# SCH_OpenIDS2.net
KiCad netlist of a schematic drawn in EasyEDA
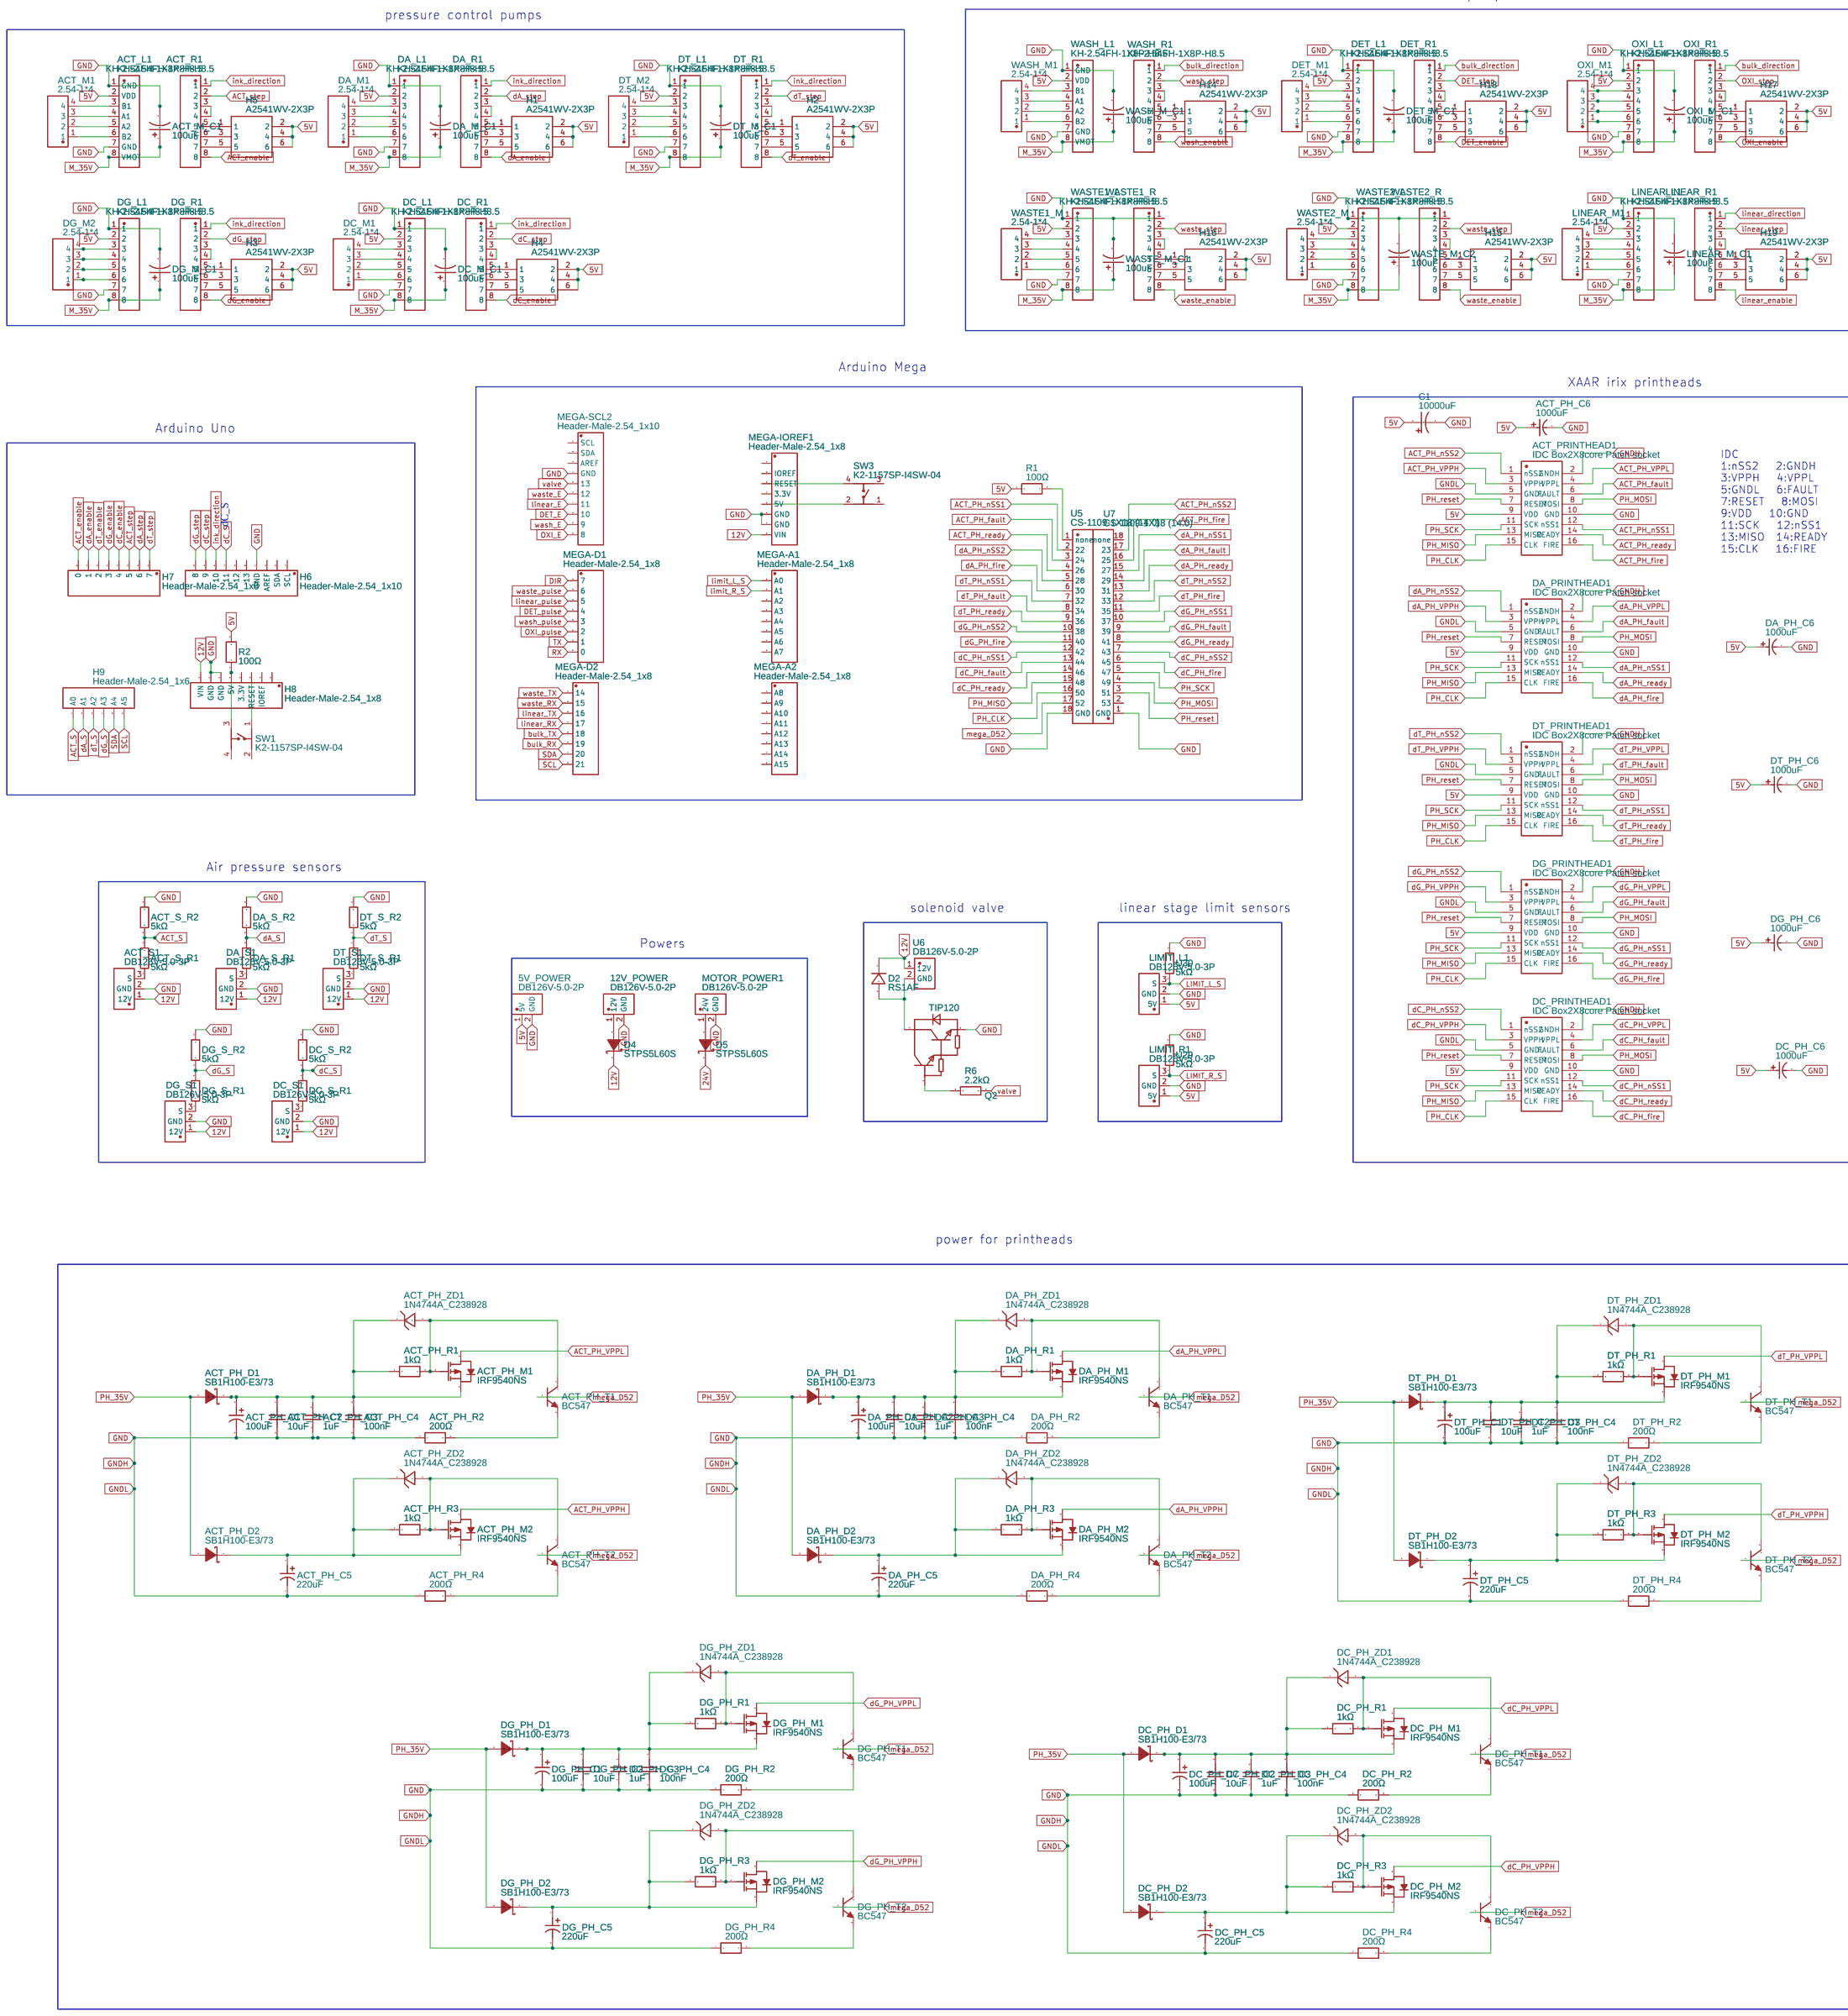
[diagram p0: schematic sheet]

(export (version "E")
  (design (tool "Eeschema 10.0.6"))
  (components
    (comp (ref "5V_POWER")
      (value "DB126V-5.0-2P")
      (fields
        (field (name "Manufacturer Part") "DB126V-5.0-2P-GN-P")
        (field (name "Manufacturer") "DORABO(地博电气)")
      )
      (libsource (lib "") (part "DB126V-5.0-2P"))
    )
    (comp (ref "12V_POWER")
      (value "DB126V-5.0-2P")
      (fields
        (field (name "Manufacturer Part") "DB126V-5.0-2P-GN-P")
        (field (name "Manufacturer") "DORABO(地博电气)")
      )
      (libsource (lib "") (part "DB126V-5.0-2P_2"))
    )
    (comp (ref "ACT_L1")
      (value "KH-2.54FH-1X8P-H8.5")
      (fields (field (name "Manufacturer") "kinghelm(金航标)"))
      (libsource (lib "") (part "KH-2.54FH-1X8P-H8.5_4"))
    )
    (comp (ref "ACT_M1")
      (value "2.54-1*4")
      (fields (field (name "Manufacturer") "ZHOURI(洲日)"))
      (libsource (lib "") (part "2.54-1*4_7"))
    )
    (comp (ref "ACT_M_C1")
      (value "100uF")
      (fields
        (field (name "Manufacturer Part") "50YXF100MEFCCE8X11.5")
        (field (name "Manufacturer") "rubycon(红宝石)")
      )
      (libsource (lib "") (part "50YXF100MEFCCE8X11.5"))
    )
    (comp (ref "ACT_PH_C1")
      (value "100uF")
      (fields (field (name "Manufacturer Part") "1011001013R00") (field (name "Manufacturer") "NJCON(永立)"))
      (libsource (lib "") (part "1011001013R00_4"))
    )
    (comp (ref "ACT_PH_C2")
      (value "10uF")
      (fields (field (name "Manufacturer Part") "C1210X106K050T") (field (name "Manufacturer") "IHHEC(禾伸堂)"))
      (libsource (lib "") (part "C1210X106K050T_3"))
    )
    (comp (ref "ACT_PH_C3")
      (value "1uF")
      (fields (field (name "Manufacturer Part") "1210B105K101NT") (field (name "Manufacturer") "FH(风华)"))
      (libsource (lib "") (part "1210B105K101NT_4"))
    )
    (comp (ref "ACT_PH_C4")
      (value "100nF")
      (fields (field (name "Manufacturer Part") "C1005X7R1H104KT000S") (field (name "Manufacturer") "TDK"))
      (libsource (lib "") (part "C1005X7R1H104KT000S"))
    )
    (comp (ref "ACT_PH_C5")
      (value "220uF")
      (fields
        (field (name "Manufacturer Part") "RVT1H221M1010 220UF 50V")
        (field (name "Manufacturer") "DMBJ(振宝佳)")
      )
      (libsource (lib "") (part "RVT1H221M1010 220UF 50V"))
    )
    (comp (ref "ACT_PH_C6")
      (value "1000uF")
      (fields (field (name "Manufacturer Part") "KF102M010F140A") (field (name "Manufacturer") "CapXon(丰宾)"))
      (libsource (lib "") (part "KF102M010F140A_4"))
    )
    (comp (ref "ACT_PH_D1")
      (value "SB1H100-E3/73")
      (fields (field (name "Manufacturer") "VISHAY(威世)"))
      (libsource (lib "") (part "SB1H100-E3/73_4"))
    )
    (comp (ref "ACT_PH_D2")
      (value "SB1H100-E3/73")
      (fields (field (name "Manufacturer") "VISHAY(威世)"))
      (libsource (lib "") (part "SB1H100-E3/73_4"))
    )
    (comp (ref "ACT_PH_M1")
      (value "IRF9540NS")
      (fields (field (name "Manufacturer") "minos(迈诺斯)"))
      (libsource (lib "") (part "IRF9540NS_4"))
    )
    (comp (ref "ACT_PH_M2")
      (value "IRF9540NS")
      (fields (field (name "Manufacturer") "minos(迈诺斯)"))
      (libsource (lib "") (part "IRF9540NS_4"))
    )
    (comp (ref "ACT_PH_R1")
      (value "1kΩ")
      (fields
        (field (name "Manufacturer Part") "HoCR2512-2W-1KR-5%")
        (field (name "Manufacturer") "Milliohm(毫欧)")
      )
      (libsource (lib "") (part "HOCR2512-2W-1KR-5%_2"))
    )
    (comp (ref "ACT_PH_R2")
      (value "200Ω")
      (fields (field (name "Manufacturer Part") "CR1/4W-200Ω±5%-ST52") (field (name "Manufacturer") "VO(翔胜)"))
      (libsource (lib "") (part "CR1/4W-200Ω±5%-ST52_4"))
    )
    (comp (ref "ACT_PH_R3")
      (value "1kΩ")
      (fields
        (field (name "Manufacturer Part") "HoCR2512-2W-1KR-5%")
        (field (name "Manufacturer") "Milliohm(毫欧)")
      )
      (libsource (lib "") (part "HOCR2512-2W-1KR-5%_2"))
    )
    (comp (ref "ACT_PH_R4")
      (value "200Ω")
      (fields (field (name "Manufacturer Part") "CR1/4W-200Ω±5%-ST52") (field (name "Manufacturer") "VO(翔胜)"))
      (libsource (lib "") (part "CR1/4W-200Ω±5%-ST52_4"))
    )
    (comp (ref "ACT_PH_T1")
      (value "BC547")
      (fields
        (field (name "Manufacturer Part") "BC547(RANGE:420-800)")
        (field (name "Manufacturer") "CJ(江苏长电/长晶)")
      )
      (libsource (lib "") (part "BC547_3"))
    )
    (comp (ref "ACT_PH_T2")
      (value "BC547")
      (fields
        (field (name "Manufacturer Part") "BC547(RANGE:420-800)")
        (field (name "Manufacturer") "CJ(江苏长电/长晶)")
      )
      (libsource (lib "") (part "BC547_3"))
    )
    (comp (ref "ACT_PH_ZD1")
      (value "1N4744A_C238928")
      (fields (field (name "Manufacturer Part") "1N4744A") (field (name "Manufacturer") "onsemi(安森美)"))
      (libsource (lib "") (part "1N4744A_C238928_1"))
    )
    (comp (ref "ACT_PH_ZD2")
      (value "1N4744A_C238928")
      (fields (field (name "Manufacturer Part") "1N4744A") (field (name "Manufacturer") "onsemi(安森美)"))
      (libsource (lib "") (part "1N4744A_C238928_1"))
    )
    (comp (ref "ACT_PRINTHEAD1")
      (value "IDC Box2X8core Patch socket")
      (fields (field (name "Manufacturer Part") "2.0-2*8P立贴简牛") (field (name "Manufacturer") "BOOMELE(博穆精密)"))
      (libsource (lib "") (part "IDC Box2X8core Patch socket"))
    )
    (comp (ref "ACT_R1")
      (value "KH-2.54FH-1X8P-H8.5")
      (fields (field (name "Manufacturer") "kinghelm(金航标)"))
      (libsource (lib "") (part "KH-2.54FH-1X8P-H8.5_7"))
    )
    (comp (ref "ACT_S1")
      (value "DB126V-5.0-3P")
      (fields
        (field (name "Manufacturer Part") "DB126V-5.0-3P-GN")
        (field (name "Manufacturer") "DORABO(地博电气)")
      )
      (libsource (lib "") (part "DB126V-5.0-3P_6"))
    )
    (comp (ref "ACT_S_R1")
      (value "5kΩ")
      (fields (field (name "Manufacturer Part") "RT0603BRE075KL") (field (name "Manufacturer") "YAGEO(国巨)"))
      (libsource (lib "") (part "RT0603BRE075KL_1"))
    )
    (comp (ref "ACT_S_R2")
      (value "5kΩ")
      (fields (field (name "Manufacturer Part") "RT0603BRE075KL") (field (name "Manufacturer") "YAGEO(国巨)"))
      (libsource (lib "") (part "RT0603BRE075KL_1"))
    )
    (comp (ref "C1")
      (value "10000uF")
      (fields
        (field (name "Manufacturer Part") "KM1C103ML350A00CV0")
        (field (name "Manufacturer") "HUAWEI(华威集团)")
      )
      (libsource (lib "") (part "KM1C103ML350A00CV0"))
    )
    (comp (ref "D2")
      (value "RS1AF")
      (fields (field (name "Manufacturer") "SHIKUES(时科)"))
      (libsource (lib "") (part "RS1AF"))
    )
    (comp (ref "D4")
      (value "STPS5L60S")
      (fields (field (name "Manufacturer") "ST(意法半导体)"))
      (libsource (lib "") (part "STPS5L60S"))
    )
    (comp (ref "D5")
      (value "STPS5L60S")
      (fields (field (name "Manufacturer") "ST(意法半导体)"))
      (libsource (lib "") (part "STPS5L60S"))
    )
    (comp (ref "DA_L1")
      (value "KH-2.54FH-1X8P-H8.5")
      (fields (field (name "Manufacturer") "kinghelm(金航标)"))
      (libsource (lib "") (part "KH-2.54FH-1X8P-H8.5_20"))
    )
    (comp (ref "DA_M1")
      (value "2.54-1*4")
      (fields (field (name "Manufacturer") "ZHOURI(洲日)"))
      (libsource (lib "") (part "2.54-1*4_6"))
    )
    (comp (ref "DA_M_C1")
      (value "100uF")
      (fields
        (field (name "Manufacturer Part") "50YXF100MEFCCE8X11.5")
        (field (name "Manufacturer") "rubycon(红宝石)")
      )
      (libsource (lib "") (part "50YXF100MEFCCE8X11.5_7"))
    )
    (comp (ref "DA_PH_C1")
      (value "100uF")
      (fields (field (name "Manufacturer Part") "1011001013R00") (field (name "Manufacturer") "NJCON(永立)"))
      (libsource (lib "") (part "1011001013R00_3"))
    )
    (comp (ref "DA_PH_C2")
      (value "10uF")
      (fields (field (name "Manufacturer Part") "C1210X106K050T") (field (name "Manufacturer") "IHHEC(禾伸堂)"))
      (libsource (lib "") (part "C1210X106K050T"))
    )
    (comp (ref "DA_PH_C3")
      (value "1uF")
      (fields (field (name "Manufacturer Part") "1210B105K101NT") (field (name "Manufacturer") "FH(风华)"))
      (libsource (lib "") (part "1210B105K101NT"))
    )
    (comp (ref "DA_PH_C4")
      (value "100nF")
      (fields (field (name "Manufacturer Part") "C1005X7R1H104KT000S") (field (name "Manufacturer") "TDK"))
      (libsource (lib "") (part "C1005X7R1H104KT000S_3"))
    )
    (comp (ref "DA_PH_C5")
      (value "220uF")
      (fields
        (field (name "Manufacturer Part") "RVT1H221M1010 220UF 50V")
        (field (name "Manufacturer") "DMBJ(振宝佳)")
      )
      (libsource (lib "") (part "RVT1H221M1010 220UF 50V_3"))
    )
    (comp (ref "DA_PH_C6")
      (value "1000uF")
      (fields (field (name "Manufacturer Part") "KF102M010F140A") (field (name "Manufacturer") "CapXon(丰宾)"))
      (libsource (lib "") (part "KF102M010F140A_2"))
    )
    (comp (ref "DA_PH_D1")
      (value "SB1H100-E3/73")
      (fields (field (name "Manufacturer") "VISHAY(威世)"))
      (libsource (lib "") (part "SB1H100-E3/73_1"))
    )
    (comp (ref "DA_PH_D2")
      (value "SB1H100-E3/73")
      (fields (field (name "Manufacturer") "VISHAY(威世)"))
      (libsource (lib "") (part "SB1H100-E3/73_1"))
    )
    (comp (ref "DA_PH_M1")
      (value "IRF9540NS")
      (fields (field (name "Manufacturer") "minos(迈诺斯)"))
      (libsource (lib "") (part "IRF9540NS_1"))
    )
    (comp (ref "DA_PH_M2")
      (value "IRF9540NS")
      (fields (field (name "Manufacturer") "minos(迈诺斯)"))
      (libsource (lib "") (part "IRF9540NS_1"))
    )
    (comp (ref "DA_PH_R1")
      (value "1kΩ")
      (fields
        (field (name "Manufacturer Part") "HoCR2512-2W-1KR-5%")
        (field (name "Manufacturer") "Milliohm(毫欧)")
      )
      (libsource (lib "") (part "HOCR2512-2W-1KR-5%"))
    )
    (comp (ref "DA_PH_R2")
      (value "200Ω")
      (fields (field (name "Manufacturer Part") "CR1/4W-200Ω±5%-ST52") (field (name "Manufacturer") "VO(翔胜)"))
      (libsource (lib "") (part "CR1/4W-200Ω±5%-ST52"))
    )
    (comp (ref "DA_PH_R3")
      (value "1kΩ")
      (fields
        (field (name "Manufacturer Part") "HoCR2512-2W-1KR-5%")
        (field (name "Manufacturer") "Milliohm(毫欧)")
      )
      (libsource (lib "") (part "HOCR2512-2W-1KR-5%"))
    )
    (comp (ref "DA_PH_R4")
      (value "200Ω")
      (fields (field (name "Manufacturer Part") "CR1/4W-200Ω±5%-ST52") (field (name "Manufacturer") "VO(翔胜)"))
      (libsource (lib "") (part "CR1/4W-200Ω±5%-ST52"))
    )
    (comp (ref "DA_PH_T1")
      (value "BC547")
      (fields
        (field (name "Manufacturer Part") "BC547(RANGE:420-800)")
        (field (name "Manufacturer") "CJ(江苏长电/长晶)")
      )
      (libsource (lib "") (part "BC547"))
    )
    (comp (ref "DA_PH_T2")
      (value "BC547")
      (fields
        (field (name "Manufacturer Part") "BC547(RANGE:420-800)")
        (field (name "Manufacturer") "CJ(江苏长电/长晶)")
      )
      (libsource (lib "") (part "BC547"))
    )
    (comp (ref "DA_PH_ZD1")
      (value "1N4744A_C238928")
      (fields (field (name "Manufacturer Part") "1N4744A") (field (name "Manufacturer") "onsemi(安森美)"))
      (libsource (lib "") (part "1N4744A_C238928"))
    )
    (comp (ref "DA_PH_ZD2")
      (value "1N4744A_C238928")
      (fields (field (name "Manufacturer Part") "1N4744A") (field (name "Manufacturer") "onsemi(安森美)"))
      (libsource (lib "") (part "1N4744A_C238928"))
    )
    (comp (ref "DA_PRINTHEAD1")
      (value "IDC Box2X8core Patch socket")
      (fields (field (name "Manufacturer Part") "2.0-2*8P立贴简牛") (field (name "Manufacturer") "BOOMELE(博穆精密)"))
      (libsource (lib "") (part "IDC Box2X8core Patch socket_1"))
    )
    (comp (ref "DA_R1")
      (value "KH-2.54FH-1X8P-H8.5")
      (fields (field (name "Manufacturer") "kinghelm(金航标)"))
      (libsource (lib "") (part "KH-2.54FH-1X8P-H8.5_15"))
    )
    (comp (ref "DA_S1")
      (value "DB126V-5.0-3P")
      (fields
        (field (name "Manufacturer Part") "DB126V-5.0-3P-GN")
        (field (name "Manufacturer") "DORABO(地博电气)")
      )
      (libsource (lib "") (part "DB126V-5.0-3P_3"))
    )
    (comp (ref "DA_S_R1")
      (value "5kΩ")
      (fields (field (name "Manufacturer Part") "RT0603BRE075KL") (field (name "Manufacturer") "YAGEO(国巨)"))
      (libsource (lib "") (part "RT0603BRE075KL"))
    )
    (comp (ref "DA_S_R2")
      (value "5kΩ")
      (fields (field (name "Manufacturer Part") "RT0603BRE075KL") (field (name "Manufacturer") "YAGEO(国巨)"))
      (libsource (lib "") (part "RT0603BRE075KL"))
    )
    (comp (ref "DC_L1")
      (value "KH-2.54FH-1X8P-H8.5")
      (fields (field (name "Manufacturer") "kinghelm(金航标)"))
      (libsource (lib "") (part "KH-2.54FH-1X8P-H8.5_5"))
    )
    (comp (ref "DC_M1")
      (value "2.54-1*4")
      (fields (field (name "Manufacturer") "ZHOURI(洲日)"))
      (libsource (lib "") (part "2.54-1*4_1"))
    )
    (comp (ref "DC_M_C1")
      (value "100uF")
      (fields
        (field (name "Manufacturer Part") "50YXF100MEFCCE8X11.5")
        (field (name "Manufacturer") "rubycon(红宝石)")
      )
      (libsource (lib "") (part "50YXF100MEFCCE8X11.5_5"))
    )
    (comp (ref "DC_PH_C2")
      (value "10uF")
      (fields (field (name "Manufacturer Part") "C1210X106K050T") (field (name "Manufacturer") "IHHEC(禾伸堂)"))
      (libsource (lib "") (part "C1210X106K050T_2"))
    )
    (comp (ref "DC_PH_C3")
      (value "1uF")
      (fields (field (name "Manufacturer Part") "1210B105K101NT") (field (name "Manufacturer") "FH(风华)"))
      (libsource (lib "") (part "1210B105K101NT_3"))
    )
    (comp (ref "DC_PH_C4")
      (value "100nF")
      (fields (field (name "Manufacturer Part") "C1005X7R1H104KT000S") (field (name "Manufacturer") "TDK"))
      (libsource (lib "") (part "C1005X7R1H104KT000S_1"))
    )
    (comp (ref "DC_PH_C5")
      (value "220uF")
      (fields
        (field (name "Manufacturer Part") "RVT1H221M1010 220UF 50V")
        (field (name "Manufacturer") "DMBJ(振宝佳)")
      )
      (libsource (lib "") (part "RVT1H221M1010 220UF 50V_1"))
    )
    (comp (ref "DC_PH_C6")
      (value "1000uF")
      (fields (field (name "Manufacturer Part") "KF102M010F140A") (field (name "Manufacturer") "CapXon(丰宾)"))
      (libsource (lib "") (part "KF102M010F140A_3"))
    )
    (comp (ref "DC_PH_C7")
      (value "100uF")
      (fields (field (name "Manufacturer Part") "1011001013R00") (field (name "Manufacturer") "NJCON(永立)"))
      (libsource (lib "") (part "1011001013R00_2"))
    )
    (comp (ref "DC_PH_D1")
      (value "SB1H100-E3/73")
      (fields (field (name "Manufacturer") "VISHAY(威世)"))
      (libsource (lib "") (part "SB1H100-E3/73"))
    )
    (comp (ref "DC_PH_D2")
      (value "SB1H100-E3/73")
      (fields (field (name "Manufacturer") "VISHAY(威世)"))
      (libsource (lib "") (part "SB1H100-E3/73"))
    )
    (comp (ref "DC_PH_M1")
      (value "IRF9540NS")
      (fields (field (name "Manufacturer") "minos(迈诺斯)"))
      (libsource (lib "") (part "IRF9540NS_2"))
    )
    (comp (ref "DC_PH_M2")
      (value "IRF9540NS")
      (fields (field (name "Manufacturer") "minos(迈诺斯)"))
      (libsource (lib "") (part "IRF9540NS_2"))
    )
    (comp (ref "DC_PH_R1")
      (value "1kΩ")
      (fields
        (field (name "Manufacturer Part") "HoCR2512-2W-1KR-5%")
        (field (name "Manufacturer") "Milliohm(毫欧)")
      )
      (libsource (lib "") (part "HOCR2512-2W-1KR-5%_3"))
    )
    (comp (ref "DC_PH_R2")
      (value "200Ω")
      (fields (field (name "Manufacturer Part") "CR1/4W-200Ω±5%-ST52") (field (name "Manufacturer") "VO(翔胜)"))
      (libsource (lib "") (part "CR1/4W-200Ω±5%-ST52_3"))
    )
    (comp (ref "DC_PH_R3")
      (value "1kΩ")
      (fields
        (field (name "Manufacturer Part") "HoCR2512-2W-1KR-5%")
        (field (name "Manufacturer") "Milliohm(毫欧)")
      )
      (libsource (lib "") (part "HOCR2512-2W-1KR-5%_3"))
    )
    (comp (ref "DC_PH_R4")
      (value "200Ω")
      (fields (field (name "Manufacturer Part") "CR1/4W-200Ω±5%-ST52") (field (name "Manufacturer") "VO(翔胜)"))
      (libsource (lib "") (part "CR1/4W-200Ω±5%-ST52_3"))
    )
    (comp (ref "DC_PH_T1")
      (value "BC547")
      (fields
        (field (name "Manufacturer Part") "BC547(RANGE:420-800)")
        (field (name "Manufacturer") "CJ(江苏长电/长晶)")
      )
      (libsource (lib "") (part "BC547_2"))
    )
    (comp (ref "DC_PH_T2")
      (value "BC547")
      (fields
        (field (name "Manufacturer Part") "BC547(RANGE:420-800)")
        (field (name "Manufacturer") "CJ(江苏长电/长晶)")
      )
      (libsource (lib "") (part "BC547_2"))
    )
    (comp (ref "DC_PH_ZD1")
      (value "1N4744A_C238928")
      (fields (field (name "Manufacturer Part") "1N4744A") (field (name "Manufacturer") "onsemi(安森美)"))
      (libsource (lib "") (part "1N4744A_C238928_2"))
    )
    (comp (ref "DC_PH_ZD2")
      (value "1N4744A_C238928")
      (fields (field (name "Manufacturer Part") "1N4744A") (field (name "Manufacturer") "onsemi(安森美)"))
      (libsource (lib "") (part "1N4744A_C238928_2"))
    )
    (comp (ref "DC_PRINTHEAD1")
      (value "IDC Box2X8core Patch socket")
      (fields (field (name "Manufacturer Part") "2.0-2*8P立贴简牛") (field (name "Manufacturer") "BOOMELE(博穆精密)"))
      (libsource (lib "") (part "IDC Box2X8core Patch socket_2"))
    )
    (comp (ref "DC_R1")
      (value "KH-2.54FH-1X8P-H8.5")
      (fields (field (name "Manufacturer") "kinghelm(金航标)"))
      (libsource (lib "") (part "KH-2.54FH-1X8P-H8.5_18"))
    )
    (comp (ref "DC_S1")
      (value "DB126V-5.0-3P")
      (fields
        (field (name "Manufacturer Part") "DB126V-5.0-3P-GN")
        (field (name "Manufacturer") "DORABO(地博电气)")
      )
      (libsource (lib "") (part "DB126V-5.0-3P_4"))
    )
    (comp (ref "DC_S_R1")
      (value "5kΩ")
      (fields (field (name "Manufacturer Part") "RT0603BRE075KL") (field (name "Manufacturer") "YAGEO(国巨)"))
      (libsource (lib "") (part "RT0603BRE075KL_2"))
    )
    (comp (ref "DC_S_R2")
      (value "5kΩ")
      (fields (field (name "Manufacturer Part") "RT0603BRE075KL") (field (name "Manufacturer") "YAGEO(国巨)"))
      (libsource (lib "") (part "RT0603BRE075KL_2"))
    )
    (comp (ref "DET_L1")
      (value "KH-2.54FH-1X8P-H8.5")
      (fields (field (name "Manufacturer") "kinghelm(金航标)"))
      (libsource (lib "") (part "KH-2.54FH-1X8P-H8.5_12"))
    )
    (comp (ref "DET_M1")
      (value "2.54-1*4")
      (fields (field (name "Manufacturer") "ZHOURI(洲日)"))
      (libsource (lib "") (part "2.54-1*4_4"))
    )
    (comp (ref "DET_M_C1")
      (value "100uF")
      (fields
        (field (name "Manufacturer Part") "50YXF100MEFCCE8X11.5")
        (field (name "Manufacturer") "rubycon(红宝石)")
      )
      (libsource (lib "") (part "50YXF100MEFCCE8X11.5_8"))
    )
    (comp (ref "DET_R1")
      (value "KH-2.54FH-1X8P-H8.5")
      (fields (field (name "Manufacturer") "kinghelm(金航标)"))
      (libsource (lib "") (part "KH-2.54FH-1X8P-H8.5_3"))
    )
    (comp (ref "DG_L1")
      (value "KH-2.54FH-1X8P-H8.5")
      (fields (field (name "Manufacturer") "kinghelm(金航标)"))
      (libsource (lib "") (part "KH-2.54FH-1X8P-H8.5_1"))
    )
    (comp (ref "DG_M2")
      (value "2.54-1*4")
      (fields (field (name "Manufacturer") "ZHOURI(洲日)"))
      (libsource (lib "") (part "2.54-1*4_5"))
    )
    (comp (ref "DG_M_C1")
      (value "100uF")
      (fields
        (field (name "Manufacturer Part") "50YXF100MEFCCE8X11.5")
        (field (name "Manufacturer") "rubycon(红宝石)")
      )
      (libsource (lib "") (part "50YXF100MEFCCE8X11.5_1"))
    )
    (comp (ref "DG_PH_C1")
      (value "100uF")
      (fields (field (name "Manufacturer Part") "1011001013R00") (field (name "Manufacturer") "NJCON(永立)"))
      (libsource (lib "") (part "1011001013R00"))
    )
    (comp (ref "DG_PH_C2")
      (value "10uF")
      (fields (field (name "Manufacturer Part") "C1210X106K050T") (field (name "Manufacturer") "IHHEC(禾伸堂)"))
      (libsource (lib "") (part "C1210X106K050T_1"))
    )
    (comp (ref "DG_PH_C3")
      (value "1uF")
      (fields (field (name "Manufacturer Part") "1210B105K101NT") (field (name "Manufacturer") "FH(风华)"))
      (libsource (lib "") (part "1210B105K101NT_2"))
    )
    (comp (ref "DG_PH_C4")
      (value "100nF")
      (fields (field (name "Manufacturer Part") "C1005X7R1H104KT000S") (field (name "Manufacturer") "TDK"))
      (libsource (lib "") (part "C1005X7R1H104KT000S_4"))
    )
    (comp (ref "DG_PH_C5")
      (value "220uF")
      (fields
        (field (name "Manufacturer Part") "RVT1H221M1010 220UF 50V")
        (field (name "Manufacturer") "DMBJ(振宝佳)")
      )
      (libsource (lib "") (part "RVT1H221M1010 220UF 50V_4"))
    )
    (comp (ref "DG_PH_C6")
      (value "1000uF")
      (fields (field (name "Manufacturer Part") "KF102M010F140A") (field (name "Manufacturer") "CapXon(丰宾)"))
      (libsource (lib "") (part "KF102M010F140A"))
    )
    (comp (ref "DG_PH_D1")
      (value "SB1H100-E3/73")
      (fields (field (name "Manufacturer") "VISHAY(威世)"))
      (libsource (lib "") (part "SB1H100-E3/73_2"))
    )
    (comp (ref "DG_PH_D2")
      (value "SB1H100-E3/73")
      (fields (field (name "Manufacturer") "VISHAY(威世)"))
      (libsource (lib "") (part "SB1H100-E3/73_2"))
    )
    (comp (ref "DG_PH_M1")
      (value "IRF9540NS")
      (fields (field (name "Manufacturer") "minos(迈诺斯)"))
      (libsource (lib "") (part "IRF9540NS_3"))
    )
    (comp (ref "DG_PH_M2")
      (value "IRF9540NS")
      (fields (field (name "Manufacturer") "minos(迈诺斯)"))
      (libsource (lib "") (part "IRF9540NS_3"))
    )
    (comp (ref "DG_PH_R1")
      (value "1kΩ")
      (fields
        (field (name "Manufacturer Part") "HoCR2512-2W-1KR-5%")
        (field (name "Manufacturer") "Milliohm(毫欧)")
      )
      (libsource (lib "") (part "HOCR2512-2W-1KR-5%_4"))
    )
    (comp (ref "DG_PH_R2")
      (value "200Ω")
      (fields (field (name "Manufacturer Part") "CR1/4W-200Ω±5%-ST52") (field (name "Manufacturer") "VO(翔胜)"))
      (libsource (lib "") (part "CR1/4W-200Ω±5%-ST52_1"))
    )
    (comp (ref "DG_PH_R3")
      (value "1kΩ")
      (fields
        (field (name "Manufacturer Part") "HoCR2512-2W-1KR-5%")
        (field (name "Manufacturer") "Milliohm(毫欧)")
      )
      (libsource (lib "") (part "HOCR2512-2W-1KR-5%_4"))
    )
    (comp (ref "DG_PH_R4")
      (value "200Ω")
      (fields (field (name "Manufacturer Part") "CR1/4W-200Ω±5%-ST52") (field (name "Manufacturer") "VO(翔胜)"))
      (libsource (lib "") (part "CR1/4W-200Ω±5%-ST52_1"))
    )
    (comp (ref "DG_PH_T1")
      (value "BC547")
      (fields
        (field (name "Manufacturer Part") "BC547(RANGE:420-800)")
        (field (name "Manufacturer") "CJ(江苏长电/长晶)")
      )
      (libsource (lib "") (part "BC547_1"))
    )
    (comp (ref "DG_PH_T2")
      (value "BC547")
      (fields
        (field (name "Manufacturer Part") "BC547(RANGE:420-800)")
        (field (name "Manufacturer") "CJ(江苏长电/长晶)")
      )
      (libsource (lib "") (part "BC547_1"))
    )
    (comp (ref "DG_PH_ZD1")
      (value "1N4744A_C238928")
      (fields (field (name "Manufacturer Part") "1N4744A") (field (name "Manufacturer") "onsemi(安森美)"))
      (libsource (lib "") (part "1N4744A_C238928_4"))
    )
    (comp (ref "DG_PH_ZD2")
      (value "1N4744A_C238928")
      (fields (field (name "Manufacturer Part") "1N4744A") (field (name "Manufacturer") "onsemi(安森美)"))
      (libsource (lib "") (part "1N4744A_C238928_4"))
    )
    (comp (ref "DG_PRINTHEAD1")
      (value "IDC Box2X8core Patch socket")
      (fields (field (name "Manufacturer Part") "2.0-2*8P立贴简牛") (field (name "Manufacturer") "BOOMELE(博穆精密)"))
      (libsource (lib "") (part "IDC Box2X8core Patch socket_3"))
    )
    (comp (ref "DG_R1")
      (value "KH-2.54FH-1X8P-H8.5")
      (fields (field (name "Manufacturer") "kinghelm(金航标)"))
      (libsource (lib "") (part "KH-2.54FH-1X8P-H8.5_21"))
    )
    (comp (ref "DG_S1")
      (value "DB126V-5.0-3P")
      (fields
        (field (name "Manufacturer Part") "DB126V-5.0-3P-GN")
        (field (name "Manufacturer") "DORABO(地博电气)")
      )
      (libsource (lib "") (part "DB126V-5.0-3P_1"))
    )
    (comp (ref "DG_S_R1")
      (value "5kΩ")
      (fields (field (name "Manufacturer Part") "RT0603BRE075KL") (field (name "Manufacturer") "YAGEO(国巨)"))
      (libsource (lib "") (part "RT0603BRE075KL_4"))
    )
    (comp (ref "DG_S_R2")
      (value "5kΩ")
      (fields (field (name "Manufacturer Part") "RT0603BRE075KL") (field (name "Manufacturer") "YAGEO(国巨)"))
      (libsource (lib "") (part "RT0603BRE075KL_4"))
    )
    (comp (ref "DT_L1")
      (value "KH-2.54FH-1X8P-H8.5")
      (fields (field (name "Manufacturer") "kinghelm(金航标)"))
      (libsource (lib "") (part "KH-2.54FH-1X8P-H8.5_13"))
    )
    (comp (ref "DT_M2")
      (value "2.54-1*4")
      (fields (field (name "Manufacturer") "ZHOURI(洲日)"))
      (libsource (lib "") (part "2.54-1*4_2"))
    )
    (comp (ref "DT_M_C1")
      (value "100uF")
      (fields
        (field (name "Manufacturer Part") "50YXF100MEFCCE8X11.5")
        (field (name "Manufacturer") "rubycon(红宝石)")
      )
      (libsource (lib "") (part "50YXF100MEFCCE8X11.5_2"))
    )
    (comp (ref "DT_PH_C1")
      (value "100uF")
      (fields (field (name "Manufacturer Part") "1011001013R00") (field (name "Manufacturer") "NJCON(永立)"))
      (libsource (lib "") (part "1011001013R00_1"))
    )
    (comp (ref "DT_PH_C2")
      (value "10uF")
      (fields (field (name "Manufacturer Part") "C1210X106K050T") (field (name "Manufacturer") "IHHEC(禾伸堂)"))
      (libsource (lib "") (part "C1210X106K050T_4"))
    )
    (comp (ref "DT_PH_C3")
      (value "1uF")
      (fields (field (name "Manufacturer Part") "1210B105K101NT") (field (name "Manufacturer") "FH(风华)"))
      (libsource (lib "") (part "1210B105K101NT_1"))
    )
    (comp (ref "DT_PH_C4")
      (value "100nF")
      (fields (field (name "Manufacturer Part") "C1005X7R1H104KT000S") (field (name "Manufacturer") "TDK"))
      (libsource (lib "") (part "C1005X7R1H104KT000S_2"))
    )
    (comp (ref "DT_PH_C5")
      (value "220uF")
      (fields
        (field (name "Manufacturer Part") "RVT1H221M1010 220UF 50V")
        (field (name "Manufacturer") "DMBJ(振宝佳)")
      )
      (libsource (lib "") (part "RVT1H221M1010 220UF 50V_2"))
    )
    (comp (ref "DT_PH_C6")
      (value "1000uF")
      (fields (field (name "Manufacturer Part") "KF102M010F140A") (field (name "Manufacturer") "CapXon(丰宾)"))
      (libsource (lib "") (part "KF102M010F140A_1"))
    )
    (comp (ref "DT_PH_D1")
      (value "SB1H100-E3/73")
      (fields (field (name "Manufacturer") "VISHAY(威世)"))
      (libsource (lib "") (part "SB1H100-E3/73_3"))
    )
    (comp (ref "DT_PH_D2")
      (value "SB1H100-E3/73")
      (fields (field (name "Manufacturer") "VISHAY(威世)"))
      (libsource (lib "") (part "SB1H100-E3/73_3"))
    )
    (comp (ref "DT_PH_M1")
      (value "IRF9540NS")
      (fields (field (name "Manufacturer") "minos(迈诺斯)"))
      (libsource (lib "") (part "IRF9540NS"))
    )
    (comp (ref "DT_PH_M2")
      (value "IRF9540NS")
      (fields (field (name "Manufacturer") "minos(迈诺斯)"))
      (libsource (lib "") (part "IRF9540NS"))
    )
    (comp (ref "DT_PH_R1")
      (value "1kΩ")
      (fields
        (field (name "Manufacturer Part") "HoCR2512-2W-1KR-5%")
        (field (name "Manufacturer") "Milliohm(毫欧)")
      )
      (libsource (lib "") (part "HOCR2512-2W-1KR-5%_1"))
    )
    (comp (ref "DT_PH_R2")
      (value "200Ω")
      (fields (field (name "Manufacturer Part") "CR1/4W-200Ω±5%-ST52") (field (name "Manufacturer") "VO(翔胜)"))
      (libsource (lib "") (part "CR1/4W-200Ω±5%-ST52_2"))
    )
    (comp (ref "DT_PH_R3")
      (value "1kΩ")
      (fields
        (field (name "Manufacturer Part") "HoCR2512-2W-1KR-5%")
        (field (name "Manufacturer") "Milliohm(毫欧)")
      )
      (libsource (lib "") (part "HOCR2512-2W-1KR-5%_1"))
    )
    (comp (ref "DT_PH_R4")
      (value "200Ω")
      (fields (field (name "Manufacturer Part") "CR1/4W-200Ω±5%-ST52") (field (name "Manufacturer") "VO(翔胜)"))
      (libsource (lib "") (part "CR1/4W-200Ω±5%-ST52_2"))
    )
    (comp (ref "DT_PH_T1")
      (value "BC547")
      (fields
        (field (name "Manufacturer Part") "BC547(RANGE:420-800)")
        (field (name "Manufacturer") "CJ(江苏长电/长晶)")
      )
      (libsource (lib "") (part "BC547_4"))
    )
    (comp (ref "DT_PH_T2")
      (value "BC547")
      (fields
        (field (name "Manufacturer Part") "BC547(RANGE:420-800)")
        (field (name "Manufacturer") "CJ(江苏长电/长晶)")
      )
      (libsource (lib "") (part "BC547_4"))
    )
    (comp (ref "DT_PH_ZD1")
      (value "1N4744A_C238928")
      (fields (field (name "Manufacturer Part") "1N4744A") (field (name "Manufacturer") "onsemi(安森美)"))
      (libsource (lib "") (part "1N4744A_C238928_3"))
    )
    (comp (ref "DT_PH_ZD2")
      (value "1N4744A_C238928")
      (fields (field (name "Manufacturer Part") "1N4744A") (field (name "Manufacturer") "onsemi(安森美)"))
      (libsource (lib "") (part "1N4744A_C238928_3"))
    )
    (comp (ref "DT_PRINTHEAD1")
      (value "IDC Box2X8core Patch socket")
      (fields (field (name "Manufacturer Part") "2.0-2*8P立贴简牛") (field (name "Manufacturer") "BOOMELE(博穆精密)"))
      (libsource (lib "") (part "IDC Box2X8core Patch socket_4"))
    )
    (comp (ref "DT_R1")
      (value "KH-2.54FH-1X8P-H8.5")
      (fields (field (name "Manufacturer") "kinghelm(金航标)"))
      (libsource (lib "") (part "KH-2.54FH-1X8P-H8.5_14"))
    )
    (comp (ref "DT_S1")
      (value "DB126V-5.0-3P")
      (fields
        (field (name "Manufacturer Part") "DB126V-5.0-3P-GN")
        (field (name "Manufacturer") "DORABO(地博电气)")
      )
      (libsource (lib "") (part "DB126V-5.0-3P_2"))
    )
    (comp (ref "DT_S_R1")
      (value "5kΩ")
      (fields (field (name "Manufacturer Part") "RT0603BRE075KL") (field (name "Manufacturer") "YAGEO(国巨)"))
      (libsource (lib "") (part "RT0603BRE075KL_3"))
    )
    (comp (ref "DT_S_R2")
      (value "5kΩ")
      (fields (field (name "Manufacturer Part") "RT0603BRE075KL") (field (name "Manufacturer") "YAGEO(国巨)"))
      (libsource (lib "") (part "RT0603BRE075KL_3"))
    )
    (comp (ref "H1")
      (value "A2541WV-2X3P")
      (fields (field (name "Manufacturer Part") "A2541WV-2x3P") (field (name "Manufacturer") "CJT(长江连接器)"))
      (libsource (lib "") (part "A2541WV-2X3P"))
    )
    (comp (ref "H2")
      (value "A2541WV-2X3P")
      (fields (field (name "Manufacturer Part") "A2541WV-2x3P") (field (name "Manufacturer") "CJT(长江连接器)"))
      (libsource (lib "") (part "A2541WV-2X3P"))
    )
    (comp (ref "H3")
      (value "A2541WV-2X3P")
      (fields (field (name "Manufacturer Part") "A2541WV-2x3P") (field (name "Manufacturer") "CJT(长江连接器)"))
      (libsource (lib "") (part "A2541WV-2X3P"))
    )
    (comp (ref "H4")
      (value "A2541WV-2X3P")
      (fields (field (name "Manufacturer Part") "A2541WV-2x3P") (field (name "Manufacturer") "CJT(长江连接器)"))
      (libsource (lib "") (part "A2541WV-2X3P"))
    )
    (comp (ref "H5")
      (value "A2541WV-2X3P")
      (fields (field (name "Manufacturer Part") "A2541WV-2x3P") (field (name "Manufacturer") "CJT(长江连接器)"))
      (libsource (lib "") (part "A2541WV-2X3P"))
    )
    (comp (ref "H6")
      (value "Header-Male-2.54_1x10")
      (fields (field (name "Manufacturer Part") "2.54-1*10P针") (field (name "Manufacturer") "BOOMELE(博穆精密)"))
      (libsource (lib "") (part "Header-Male-2.54_1x10"))
    )
    (comp (ref "H7")
      (value "Header-Male-2.54_1x8")
      (fields (field (name "Manufacturer Part") "B-2100S08P-A110") (field (name "Manufacturer") "Ckmtw(灿科盟)"))
      (libsource (lib "") (part "Header-Male-2.54_1x8"))
    )
    (comp (ref "H8")
      (value "Header-Male-2.54_1x8")
      (fields (field (name "Manufacturer Part") "B-2100S08P-A110") (field (name "Manufacturer") "Ckmtw(灿科盟)"))
      (libsource (lib "") (part "Header-Male-2.54_1x8_2"))
    )
    (comp (ref "H9")
      (value "Header-Male-2.54_1x6")
      (fields (field (name "Manufacturer Part") "2.54-1x6P直针") (field (name "Manufacturer") "BOOMELE(博穆精密)"))
      (libsource (lib "") (part "Header-Male-2.54_1x6"))
    )
    (comp (ref "H14")
      (value "A2541WV-2X3P")
      (fields (field (name "Manufacturer Part") "A2541WV-2x3P") (field (name "Manufacturer") "CJT(长江连接器)"))
      (libsource (lib "") (part "A2541WV-2X3P"))
    )
    (comp (ref "H15")
      (value "A2541WV-2X3P")
      (fields (field (name "Manufacturer Part") "A2541WV-2x3P") (field (name "Manufacturer") "CJT(长江连接器)"))
      (libsource (lib "") (part "A2541WV-2X3P"))
    )
    (comp (ref "H16")
      (value "A2541WV-2X3P")
      (fields (field (name "Manufacturer Part") "A2541WV-2x3P") (field (name "Manufacturer") "CJT(长江连接器)"))
      (libsource (lib "") (part "A2541WV-2X3P"))
    )
    (comp (ref "H17")
      (value "A2541WV-2X3P")
      (fields (field (name "Manufacturer Part") "A2541WV-2x3P") (field (name "Manufacturer") "CJT(长江连接器)"))
      (libsource (lib "") (part "A2541WV-2X3P"))
    )
    (comp (ref "H18")
      (value "A2541WV-2X3P")
      (fields (field (name "Manufacturer Part") "A2541WV-2x3P") (field (name "Manufacturer") "CJT(长江连接器)"))
      (libsource (lib "") (part "A2541WV-2X3P"))
    )
    (comp (ref "H19")
      (value "A2541WV-2X3P")
      (fields (field (name "Manufacturer Part") "A2541WV-2x3P") (field (name "Manufacturer") "CJT(长江连接器)"))
      (libsource (lib "") (part "A2541WV-2X3P"))
    )
    (comp (ref "LIMIT_L1")
      (value "DB126V-5.0-3P")
      (fields
        (field (name "Manufacturer Part") "DB126V-5.0-3P-GN")
        (field (name "Manufacturer") "DORABO(地博电气)")
      )
      (libsource (lib "") (part "DB126V-5.0-3P"))
    )
    (comp (ref "LIMIT_R1")
      (value "DB126V-5.0-3P")
      (fields
        (field (name "Manufacturer Part") "DB126V-5.0-3P-GN")
        (field (name "Manufacturer") "DORABO(地博电气)")
      )
      (libsource (lib "") (part "DB126V-5.0-3P_5"))
    )
    (comp (ref "LINEAR_L1")
      (value "KH-2.54FH-1X8P-H8.5")
      (fields (field (name "Manufacturer") "kinghelm(金航标)"))
      (libsource (lib "") (part "KH-2.54FH-1X8P-H8.5_8"))
    )
    (comp (ref "LINEAR_M1")
      (value "2.54-1*4")
      (fields (field (name "Manufacturer") "ZHOURI(洲日)"))
      (libsource (lib "") (part "2.54-1*4_3"))
    )
    (comp (ref "LINEAR_M_C1")
      (value "100uF")
      (fields
        (field (name "Manufacturer Part") "50YXF100MEFCCE8X11.5")
        (field (name "Manufacturer") "rubycon(红宝石)")
      )
      (libsource (lib "") (part "50YXF100MEFCCE8X11.5_3"))
    )
    (comp (ref "LINEAR_R1")
      (value "KH-2.54FH-1X8P-H8.5")
      (fields (field (name "Manufacturer") "kinghelm(金航标)"))
      (libsource (lib "") (part "KH-2.54FH-1X8P-H8.5_9"))
    )
    (comp (ref "MEGA-A1")
      (value "Header-Male-2.54_1x8")
      (fields (field (name "Manufacturer Part") "B-2100S08P-A110") (field (name "Manufacturer") "Ckmtw(灿科盟)"))
      (libsource (lib "") (part "Header-Male-2.54_1x8_3"))
    )
    (comp (ref "MEGA-A2")
      (value "Header-Male-2.54_1x8")
      (fields (field (name "Manufacturer Part") "B-2100S08P-A110") (field (name "Manufacturer") "Ckmtw(灿科盟)"))
      (libsource (lib "") (part "Header-Male-2.54_1x8_6"))
    )
    (comp (ref "MEGA-D1")
      (value "Header-Male-2.54_1x8")
      (fields (field (name "Manufacturer Part") "B-2100S08P-A110") (field (name "Manufacturer") "Ckmtw(灿科盟)"))
      (libsource (lib "") (part "Header-Male-2.54_1x8_5"))
    )
    (comp (ref "MEGA-D2")
      (value "Header-Male-2.54_1x8")
      (fields (field (name "Manufacturer Part") "B-2100S08P-A110") (field (name "Manufacturer") "Ckmtw(灿科盟)"))
      (libsource (lib "") (part "Header-Male-2.54_1x8_4"))
    )
    (comp (ref "MEGA-IOREF1")
      (value "Header-Male-2.54_1x8")
      (fields (field (name "Manufacturer Part") "B-2100S08P-A110") (field (name "Manufacturer") "Ckmtw(灿科盟)"))
      (libsource (lib "") (part "Header-Male-2.54_1x8_1"))
    )
    (comp (ref "MEGA-SCL2")
      (value "Header-Male-2.54_1x10")
      (fields (field (name "Manufacturer Part") "2.54-1*10P针") (field (name "Manufacturer") "BOOMELE(博穆精密)"))
      (libsource (lib "") (part "Header-Male-2.54_1x10_1"))
    )
    (comp (ref "MOTOR_POWER1")
      (value "DB126V-5.0-2P")
      (fields
        (field (name "Manufacturer Part") "DB126V-5.0-2P-GN-P")
        (field (name "Manufacturer") "DORABO(地博电气)")
      )
      (libsource (lib "") (part "DB126V-5.0-2P_3"))
    )
    (comp (ref "OXI_L1")
      (value "KH-2.54FH-1X8P-H8.5")
      (fields (field (name "Manufacturer") "kinghelm(金航标)"))
      (libsource (lib "") (part "KH-2.54FH-1X8P-H8.5_6"))
    )
    (comp (ref "OXI_M1")
      (value "2.54-1*4")
      (fields (field (name "Manufacturer") "ZHOURI(洲日)"))
      (libsource (lib "") (part "2.54-1*4"))
    )
    (comp (ref "OXI_M_C1")
      (value "100uF")
      (fields
        (field (name "Manufacturer Part") "50YXF100MEFCCE8X11.5")
        (field (name "Manufacturer") "rubycon(红宝石)")
      )
      (libsource (lib "") (part "50YXF100MEFCCE8X11.5_4"))
    )
    (comp (ref "OXI_R1")
      (value "KH-2.54FH-1X8P-H8.5")
      (fields (field (name "Manufacturer") "kinghelm(金航标)"))
      (libsource (lib "") (part "KH-2.54FH-1X8P-H8.5"))
    )
    (comp (ref "Q2")
      (value "TIP120")
      (fields (field (name "Manufacturer") "ST(意法半导体)"))
      (libsource (lib "") (part "TIP120"))
    )
    (comp (ref "R1")
      (value "100Ω")
      (fields
        (field (name "Manufacturer Part") "CMB02070X1000GB200")
        (field (name "Manufacturer") "VISHAY(威世)")
      )
      (libsource (lib "") (part "CMB02070X1000GB200"))
    )
    (comp (ref "R2")
      (value "100Ω")
      (fields
        (field (name "Manufacturer Part") "CMB02070X1000GB200")
        (field (name "Manufacturer") "VISHAY(威世)")
      )
      (libsource (lib "") (part "CMB02070X1000GB200_1"))
    )
    (comp (ref "R6")
      (value "2.2kΩ")
      (fields (field (name "Manufacturer Part") "RMC08052.2K1%N") (field (name "Manufacturer") "Tyohm(幸亚电阻)"))
      (libsource (lib "") (part "RMC08052.2K1%N"))
    )
    (comp (ref "SW1")
      (value "K2-1157SP-I4SW-04")
      (fields (field (name "Manufacturer Part") "K2-1157SP-I4SW-01") (field (name "Manufacturer") "韩国韩荣"))
      (libsource (lib "") (part "K2-1157SP-I4SW-04"))
    )
    (comp (ref "SW3")
      (value "K2-1157SP-I4SW-04")
      (fields (field (name "Manufacturer Part") "K2-1157SP-I4SW-01") (field (name "Manufacturer") "韩国韩荣"))
      (libsource (lib "") (part "K2-1157SP-I4SW-04_1"))
    )
    (comp (ref "U5")
      (value "CS-1109-1X18 (14.0)")
      (fields (field (name "Manufacturer") "CST(永丰盈)"))
      (libsource (lib "") (part "CS-1109-1X18 (14.0)"))
    )
    (comp (ref "U6")
      (value "DB126V-5.0-2P")
      (fields
        (field (name "Manufacturer Part") "DB126V-5.0-2P-GN-P")
        (field (name "Manufacturer") "DORABO(地博电气)")
      )
      (libsource (lib "") (part "DB126V-5.0-2P_1"))
    )
    (comp (ref "U7")
      (value "CS-1109-1X18 (14.0)")
      (fields (field (name "Manufacturer") "CST(永丰盈)"))
      (libsource (lib "") (part "CS-1109-1X18 (14.0)_1"))
    )
    (comp (ref "U29")
      (value "5kΩ")
      (fields
        (field (name "Manufacturer Part") "TR0603B5K00P0525Z")
        (field (name "Manufacturer") "EVER OHMS(天二科技)")
      )
      (libsource (lib "") (part "TR0603B5K00P0525Z"))
    )
    (comp (ref "U30")
      (value "5kΩ")
      (fields
        (field (name "Manufacturer Part") "TR0603B5K00P0525Z")
        (field (name "Manufacturer") "EVER OHMS(天二科技)")
      )
      (libsource (lib "") (part "TR0603B5K00P0525Z_1"))
    )
    (comp (ref "WASH_L1")
      (value "KH-2.54FH-1X8P-H8.5")
      (fields (field (name "Manufacturer") "kinghelm(金航标)"))
      (libsource (lib "") (part "KH-2.54FH-1X8P-H8.5_16"))
    )
    (comp (ref "WASH_M1")
      (value "2.54-1*4")
      (fields (field (name "Manufacturer") "ZHOURI(洲日)"))
      (libsource (lib "") (part "2.54-1*4_10"))
    )
    (comp (ref "WASH_M_C1")
      (value "100uF")
      (fields
        (field (name "Manufacturer Part") "50YXF100MEFCCE8X11.5")
        (field (name "Manufacturer") "rubycon(红宝石)")
      )
      (libsource (lib "") (part "50YXF100MEFCCE8X11.5_9"))
    )
    (comp (ref "WASH_R1")
      (value "KH-2.54FH-1X8P-H8.5")
      (fields (field (name "Manufacturer") "kinghelm(金航标)"))
      (libsource (lib "") (part "KH-2.54FH-1X8P-H8.5_2"))
    )
    (comp (ref "WASTE1_L")
      (value "KH-2.54FH-1X8P-H8.5")
      (fields (field (name "Manufacturer") "kinghelm(金航标)"))
      (libsource (lib "") (part "KH-2.54FH-1X8P-H8.5_11"))
    )
    (comp (ref "WASTE1_M")
      (value "2.54-1*4")
      (fields (field (name "Manufacturer") "ZHOURI(洲日)"))
      (libsource (lib "") (part "2.54-1*4_9"))
    )
    (comp (ref "WASTE1_R")
      (value "KH-2.54FH-1X8P-H8.5")
      (fields (field (name "Manufacturer") "kinghelm(金航标)"))
      (libsource (lib "") (part "KH-2.54FH-1X8P-H8.5_17"))
    )
    (comp (ref "WASTE2_L")
      (value "KH-2.54FH-1X8P-H8.5")
      (fields (field (name "Manufacturer") "kinghelm(金航标)"))
      (libsource (lib "") (part "KH-2.54FH-1X8P-H8.5_10"))
    )
    (comp (ref "WASTE2_M")
      (value "2.54-1*4")
      (fields (field (name "Manufacturer") "ZHOURI(洲日)"))
      (libsource (lib "") (part "2.54-1*4_8"))
    )
    (comp (ref "WASTE2_R")
      (value "KH-2.54FH-1X8P-H8.5")
      (fields (field (name "Manufacturer") "kinghelm(金航标)"))
      (libsource (lib "") (part "KH-2.54FH-1X8P-H8.5_19"))
    )
    (comp (ref "WASTE_M_C1")
      (value "100uF")
      (fields
        (field (name "Manufacturer Part") "50YXF100MEFCCE8X11.5")
        (field (name "Manufacturer") "rubycon(红宝石)")
      )
      (libsource (lib "") (part "50YXF100MEFCCE8X11.5_6"))
    )
    (comp (ref "WASTE_M_C2")
      (value "100uF")
      (fields
        (field (name "Manufacturer Part") "50YXF100MEFCCE8X11.5")
        (field (name "Manufacturer") "rubycon(红宝石)")
      )
      (libsource (lib "") (part "50YXF100MEFCCE8X11.5_6"))
    )
  )
  (nets
    (net (code "1") (name "5V") (class "Default")
      (node (ref "5V_POWER") (pin "1") (pinfunction "5V_1") (pintype "unspecified"))
      (node (ref "ACT_L1") (pin "2") (pinfunction "VDD_2") (pintype "unspecified"))
      (node (ref "ACT_PH_C6") (pin "1") (pinfunction "1_1") (pintype "input"))
      (node (ref "ACT_PRINTHEAD1") (pin "9") (pinfunction "VDD_9") (pintype "unspecified"))
      (node (ref "C1") (pin "1") (pinfunction "1_1") (pintype "unspecified"))
      (node (ref "DA_L1") (pin "2") (pinfunction "2_2") (pintype "unspecified"))
      (node (ref "DA_PH_C6") (pin "1") (pinfunction "1_1") (pintype "input"))
      (node (ref "DA_PRINTHEAD1") (pin "9") (pinfunction "VDD_9") (pintype "unspecified"))
      (node (ref "DC_L1") (pin "2") (pinfunction "2_2") (pintype "unspecified"))
      (node (ref "DC_PH_C6") (pin "1") (pinfunction "1_1") (pintype "input"))
      (node (ref "DC_PRINTHEAD1") (pin "9") (pinfunction "VDD_9") (pintype "unspecified"))
      (node (ref "DET_L1") (pin "2") (pinfunction "2_2") (pintype "unspecified"))
      (node (ref "DG_L1") (pin "2") (pinfunction "2_2") (pintype "unspecified"))
      (node (ref "DG_PH_C6") (pin "1") (pinfunction "1_1") (pintype "input"))
      (node (ref "DG_PRINTHEAD1") (pin "9") (pinfunction "VDD_9") (pintype "unspecified"))
      (node (ref "DT_L1") (pin "2") (pinfunction "2_2") (pintype "unspecified"))
      (node (ref "DT_PH_C6") (pin "1") (pinfunction "1_1") (pintype "input"))
      (node (ref "DT_PRINTHEAD1") (pin "9") (pinfunction "VDD_9") (pintype "unspecified"))
      (node (ref "H1") (pin "2") (pinfunction "2_2") (pintype "unspecified"))
      (node (ref "H1") (pin "4") (pinfunction "4_4") (pintype "unspecified"))
      (node (ref "H1") (pin "6") (pinfunction "6_6") (pintype "unspecified"))
      (node (ref "H14") (pin "2") (pinfunction "2_2") (pintype "unspecified"))
      (node (ref "H14") (pin "4") (pinfunction "4_4") (pintype "unspecified"))
      (node (ref "H14") (pin "6") (pinfunction "6_6") (pintype "unspecified"))
      (node (ref "H15") (pin "2") (pinfunction "2_2") (pintype "unspecified"))
      (node (ref "H15") (pin "4") (pinfunction "4_4") (pintype "unspecified"))
      (node (ref "H15") (pin "6") (pinfunction "6_6") (pintype "unspecified"))
      (node (ref "H16") (pin "2") (pinfunction "2_2") (pintype "unspecified"))
      (node (ref "H16") (pin "4") (pinfunction "4_4") (pintype "unspecified"))
      (node (ref "H16") (pin "6") (pinfunction "6_6") (pintype "unspecified"))
      (node (ref "H17") (pin "2") (pinfunction "2_2") (pintype "unspecified"))
      (node (ref "H17") (pin "4") (pinfunction "4_4") (pintype "unspecified"))
      (node (ref "H17") (pin "6") (pinfunction "6_6") (pintype "unspecified"))
      (node (ref "H18") (pin "2") (pinfunction "2_2") (pintype "unspecified"))
      (node (ref "H18") (pin "4") (pinfunction "4_4") (pintype "unspecified"))
      (node (ref "H18") (pin "6") (pinfunction "6_6") (pintype "unspecified"))
      (node (ref "H19") (pin "2") (pinfunction "2_2") (pintype "unspecified"))
      (node (ref "H19") (pin "4") (pinfunction "4_4") (pintype "unspecified"))
      (node (ref "H19") (pin "6") (pinfunction "6_6") (pintype "unspecified"))
      (node (ref "H2") (pin "2") (pinfunction "2_2") (pintype "unspecified"))
      (node (ref "H2") (pin "4") (pinfunction "4_4") (pintype "unspecified"))
      (node (ref "H2") (pin "6") (pinfunction "6_6") (pintype "unspecified"))
      (node (ref "H3") (pin "2") (pinfunction "2_2") (pintype "unspecified"))
      (node (ref "H3") (pin "4") (pinfunction "4_4") (pintype "unspecified"))
      (node (ref "H3") (pin "6") (pinfunction "6_6") (pintype "unspecified"))
      (node (ref "H4") (pin "2") (pinfunction "2_2") (pintype "unspecified"))
      (node (ref "H4") (pin "4") (pinfunction "4_4") (pintype "unspecified"))
      (node (ref "H4") (pin "6") (pinfunction "6_6") (pintype "unspecified"))
      (node (ref "H5") (pin "2") (pinfunction "2_2") (pintype "unspecified"))
      (node (ref "H5") (pin "4") (pinfunction "4_4") (pintype "unspecified"))
      (node (ref "H5") (pin "6") (pinfunction "6_6") (pintype "unspecified"))
      (node (ref "LIMIT_L1") (pin "1") (pinfunction "5V_1") (pintype "unspecified"))
      (node (ref "LIMIT_R1") (pin "1") (pinfunction "5V_1") (pintype "unspecified"))
      (node (ref "LINEAR_L1") (pin "2") (pinfunction "2_2") (pintype "unspecified"))
      (node (ref "OXI_L1") (pin "2") (pinfunction "2_2") (pintype "unspecified"))
      (node (ref "R1") (pin "1") (pinfunction "1_1") (pintype "unspecified"))
      (node (ref "R2") (pin "2") (pinfunction "2_2") (pintype "unspecified"))
      (node (ref "WASH_L1") (pin "2") (pinfunction "VDD_2") (pintype "unspecified"))
      (node (ref "WASTE1_L") (pin "2") (pinfunction "2_2") (pintype "unspecified"))
      (node (ref "WASTE2_L") (pin "2") (pinfunction "2_2") (pintype "unspecified"))
    )
    (net (code "2") (name "12V") (class "Default")
      (node (ref "ACT_S1") (pin "1") (pinfunction "12V_1") (pintype "unspecified"))
      (node (ref "D2") (pin "1") (pinfunction "1_1") (pintype "unspecified"))
      (node (ref "D4") (pin "1") (pinfunction "C_1") (pintype "unspecified"))
      (node (ref "DA_S1") (pin "1") (pinfunction "12V_1") (pintype "unspecified"))
      (node (ref "DC_S1") (pin "1") (pinfunction "12V_1") (pintype "unspecified"))
      (node (ref "DG_S1") (pin "1") (pinfunction "12V_1") (pintype "unspecified"))
      (node (ref "DT_S1") (pin "1") (pinfunction "12V_1") (pintype "unspecified"))
      (node (ref "H8") (pin "8") (pinfunction "VIN_8") (pintype "unspecified"))
      (node (ref "MEGA-IOREF1") (pin "8") (pinfunction "VIN_8") (pintype "unspecified"))
      (node (ref "U6") (pin "1") (pinfunction "12V_1") (pintype "unspecified"))
    )
    (net (code "3") (name "24V") (class "Default")
      (node (ref "D5") (pin "1") (pinfunction "C_1") (pintype "unspecified"))
    )
    (net (code "4") (name "ACT_PH_VPPH") (class "Default")
      (node (ref "ACT_PH_M2") (pin "2") (pinfunction "D_2") (pintype "unspecified"))
      (node (ref "ACT_PRINTHEAD1") (pin "3") (pinfunction "VPPH_3") (pintype "unspecified"))
    )
    (net (code "5") (name "ACT_PH_VPPL") (class "Default")
      (node (ref "ACT_PH_M1") (pin "2") (pinfunction "D_2") (pintype "unspecified"))
      (node (ref "ACT_PRINTHEAD1") (pin "4") (pinfunction "VPPL_4") (pintype "unspecified"))
    )
    (net (code "6") (name "ACT_PH_fault") (class "Default")
      (node (ref "ACT_PRINTHEAD1") (pin "6") (pinfunction "FAULT_6") (pintype "unspecified"))
      (node (ref "U5") (pin "3") (pinfunction "24_3") (pintype "unspecified"))
    )
    (net (code "7") (name "ACT_PH_fire") (class "Default")
      (node (ref "ACT_PRINTHEAD1") (pin "16") (pinfunction "FIRE_16") (pintype "unspecified"))
      (node (ref "U7") (pin "16") (pinfunction "25_16") (pintype "unspecified"))
    )
    (net (code "8") (name "ACT_PH_nSS1") (class "Default")
      (node (ref "ACT_PRINTHEAD1") (pin "12") (pinfunction "nSS1_12") (pintype "unspecified"))
      (node (ref "U5") (pin "2") (pinfunction "22_2") (pintype "unspecified"))
    )
    (net (code "9") (name "ACT_PH_nSS2") (class "Default")
      (node (ref "ACT_PRINTHEAD1") (pin "1") (pinfunction "nSS2_1") (pintype "unspecified"))
      (node (ref "U7") (pin "17") (pinfunction "23_17") (pintype "unspecified"))
    )
    (net (code "10") (name "ACT_PH_ready") (class "Default")
      (node (ref "ACT_PRINTHEAD1") (pin "14") (pinfunction "READY_14") (pintype "unspecified"))
      (node (ref "U5") (pin "4") (pinfunction "26_4") (pintype "unspecified"))
    )
    (net (code "11") (name "ACT_S") (class "Default")
      (node (ref "ACT_S_R1") (pin "2") (pinfunction "2_2") (pintype "unspecified"))
      (node (ref "ACT_S_R2") (pin "1") (pinfunction "1_1") (pintype "unspecified"))
      (node (ref "H9") (pin "1") (pinfunction "A0_1") (pintype "input"))
    )
    (net (code "12") (name "ACT_enable") (class "Default")
      (node (ref "ACT_R1") (pin "8") (pinfunction "8_8") (pintype "unspecified"))
      (node (ref "H7") (pin "8") (pinfunction "0_8") (pintype "unspecified"))
    )
    (net (code "13") (name "ACT_step") (class "Default")
      (node (ref "ACT_R1") (pin "2") (pinfunction "2_2") (pintype "unspecified"))
      (node (ref "H7") (pin "3") (pinfunction "5_3") (pintype "unspecified"))
    )
    (net (code "14") (name "DET_E") (class "Default")
      (node (ref "MEGA-SCL2") (pin "8") (pinfunction "10_8") (pintype "unspecified"))
    )
    (net (code "15") (name "DET_enable") (class "Default")
      (node (ref "DET_R1") (pin "8") (pinfunction "8_8") (pintype "unspecified"))
    )
    (net (code "16") (name "DET_pulse") (class "Default")
      (node (ref "MEGA-D1") (pin "4") (pinfunction "4_4") (pintype "unspecified"))
    )
    (net (code "17") (name "DET_step") (class "Default")
      (node (ref "DET_R1") (pin "2") (pinfunction "2_2") (pintype "unspecified"))
    )
    (net (code "18") (name "DIR") (class "Default")
      (node (ref "MEGA-D1") (pin "1") (pinfunction "7_1") (pintype "unspecified"))
    )
    (net (code "19") (name "GND") (class "Default")
      (node (ref "12V_POWER") (pin "2") (pinfunction "GND_2") (pintype "unspecified"))
      (node (ref "5V_POWER") (pin "2") (pinfunction "GND_2") (pintype "unspecified"))
      (node (ref "ACT_L1") (pin "1") (pinfunction "GND_1") (pintype "unspecified"))
      (node (ref "ACT_L1") (pin "7") (pinfunction "GND_7") (pintype "unspecified"))
      (node (ref "ACT_M_C1") (pin "2") (pinfunction "2_2") (pintype "unspecified"))
      (node (ref "ACT_PH_C1") (pin "2") (pinfunction "2_2") (pintype "input"))
      (node (ref "ACT_PH_C2") (pin "2") (pinfunction "2_2") (pintype "unspecified"))
      (node (ref "ACT_PH_C3") (pin "1") (pinfunction "1_1") (pintype "input"))
      (node (ref "ACT_PH_C4") (pin "1") (pinfunction "1_1") (pintype "unspecified"))
      (node (ref "ACT_PH_C5") (pin "2") (pinfunction "2_2") (pintype "input"))
      (node (ref "ACT_PH_C6") (pin "2") (pinfunction "2_2") (pintype "input"))
      (node (ref "ACT_PH_R2") (pin "1") (pinfunction "1_1") (pintype "unspecified"))
      (node (ref "ACT_PH_R4") (pin "1") (pinfunction "1_1") (pintype "unspecified"))
      (node (ref "ACT_PRINTHEAD1") (pin "10") (pinfunction "GND_10") (pintype "unspecified"))
      (node (ref "ACT_PRINTHEAD1") (pin "2") (pinfunction "GNDH_2") (pintype "unspecified"))
      (node (ref "ACT_PRINTHEAD1") (pin "5") (pinfunction "GNDL_5") (pintype "unspecified"))
      (node (ref "ACT_S1") (pin "2") (pinfunction "GND_2") (pintype "unspecified"))
      (node (ref "ACT_S_R2") (pin "2") (pinfunction "2_2") (pintype "unspecified"))
      (node (ref "C1") (pin "2") (pinfunction "2_2") (pintype "unspecified"))
      (node (ref "DA_L1") (pin "1") (pinfunction "1_1") (pintype "unspecified"))
      (node (ref "DA_L1") (pin "7") (pinfunction "7_7") (pintype "unspecified"))
      (node (ref "DA_M_C1") (pin "2") (pinfunction "2_2") (pintype "unspecified"))
      (node (ref "DA_PH_C1") (pin "2") (pinfunction "2_2") (pintype "input"))
      (node (ref "DA_PH_C2") (pin "2") (pinfunction "2_2") (pintype "unspecified"))
      (node (ref "DA_PH_C3") (pin "1") (pinfunction "1_1") (pintype "input"))
      (node (ref "DA_PH_C4") (pin "1") (pinfunction "1_1") (pintype "unspecified"))
      (node (ref "DA_PH_C5") (pin "2") (pinfunction "2_2") (pintype "input"))
      (node (ref "DA_PH_C6") (pin "2") (pinfunction "2_2") (pintype "input"))
      (node (ref "DA_PH_R2") (pin "1") (pinfunction "1_1") (pintype "unspecified"))
      (node (ref "DA_PH_R4") (pin "1") (pinfunction "1_1") (pintype "unspecified"))
      (node (ref "DA_PRINTHEAD1") (pin "10") (pinfunction "GND_10") (pintype "unspecified"))
      (node (ref "DA_PRINTHEAD1") (pin "2") (pinfunction "GNDH_2") (pintype "unspecified"))
      (node (ref "DA_PRINTHEAD1") (pin "5") (pinfunction "GNDL_5") (pintype "unspecified"))
      (node (ref "DA_S1") (pin "2") (pinfunction "GND_2") (pintype "unspecified"))
      (node (ref "DA_S_R2") (pin "2") (pinfunction "2_2") (pintype "unspecified"))
      (node (ref "DC_L1") (pin "1") (pinfunction "1_1") (pintype "unspecified"))
      (node (ref "DC_L1") (pin "7") (pinfunction "7_7") (pintype "unspecified"))
      (node (ref "DC_M_C1") (pin "2") (pinfunction "2_2") (pintype "unspecified"))
      (node (ref "DC_PH_C2") (pin "2") (pinfunction "2_2") (pintype "unspecified"))
      (node (ref "DC_PH_C3") (pin "1") (pinfunction "1_1") (pintype "input"))
      (node (ref "DC_PH_C4") (pin "1") (pinfunction "1_1") (pintype "unspecified"))
      (node (ref "DC_PH_C5") (pin "2") (pinfunction "2_2") (pintype "input"))
      (node (ref "DC_PH_C6") (pin "2") (pinfunction "2_2") (pintype "input"))
      (node (ref "DC_PH_C7") (pin "2") (pinfunction "2_2") (pintype "input"))
      (node (ref "DC_PH_R2") (pin "1") (pinfunction "1_1") (pintype "unspecified"))
      (node (ref "DC_PH_R4") (pin "1") (pinfunction "1_1") (pintype "unspecified"))
      (node (ref "DC_PRINTHEAD1") (pin "10") (pinfunction "GND_10") (pintype "unspecified"))
      (node (ref "DC_PRINTHEAD1") (pin "2") (pinfunction "GNDH_2") (pintype "unspecified"))
      (node (ref "DC_PRINTHEAD1") (pin "5") (pinfunction "GNDL_5") (pintype "unspecified"))
      (node (ref "DC_S1") (pin "2") (pinfunction "GND_2") (pintype "unspecified"))
      (node (ref "DC_S_R2") (pin "2") (pinfunction "2_2") (pintype "unspecified"))
      (node (ref "DET_L1") (pin "1") (pinfunction "1_1") (pintype "unspecified"))
      (node (ref "DET_L1") (pin "7") (pinfunction "7_7") (pintype "unspecified"))
      (node (ref "DET_M_C1") (pin "2") (pinfunction "2_2") (pintype "unspecified"))
      (node (ref "DG_L1") (pin "1") (pinfunction "1_1") (pintype "unspecified"))
      (node (ref "DG_L1") (pin "7") (pinfunction "7_7") (pintype "unspecified"))
      (node (ref "DG_M_C1") (pin "2") (pinfunction "2_2") (pintype "unspecified"))
      (node (ref "DG_PH_C1") (pin "2") (pinfunction "2_2") (pintype "input"))
      (node (ref "DG_PH_C2") (pin "2") (pinfunction "2_2") (pintype "unspecified"))
      (node (ref "DG_PH_C3") (pin "1") (pinfunction "1_1") (pintype "input"))
      (node (ref "DG_PH_C4") (pin "1") (pinfunction "1_1") (pintype "unspecified"))
      (node (ref "DG_PH_C5") (pin "2") (pinfunction "2_2") (pintype "input"))
      (node (ref "DG_PH_C6") (pin "2") (pinfunction "2_2") (pintype "input"))
      (node (ref "DG_PH_R2") (pin "1") (pinfunction "1_1") (pintype "unspecified"))
      (node (ref "DG_PH_R4") (pin "1") (pinfunction "1_1") (pintype "unspecified"))
      (node (ref "DG_PRINTHEAD1") (pin "10") (pinfunction "GND_10") (pintype "unspecified"))
      (node (ref "DG_PRINTHEAD1") (pin "2") (pinfunction "GNDH_2") (pintype "unspecified"))
      (node (ref "DG_PRINTHEAD1") (pin "5") (pinfunction "GNDL_5") (pintype "unspecified"))
      (node (ref "DG_S1") (pin "2") (pinfunction "GND_2") (pintype "unspecified"))
      (node (ref "DG_S_R2") (pin "2") (pinfunction "2_2") (pintype "unspecified"))
      (node (ref "DT_L1") (pin "1") (pinfunction "1_1") (pintype "unspecified"))
      (node (ref "DT_L1") (pin "7") (pinfunction "7_7") (pintype "unspecified"))
      (node (ref "DT_M_C1") (pin "2") (pinfunction "2_2") (pintype "unspecified"))
      (node (ref "DT_PH_C1") (pin "2") (pinfunction "2_2") (pintype "input"))
      (node (ref "DT_PH_C2") (pin "2") (pinfunction "2_2") (pintype "unspecified"))
      (node (ref "DT_PH_C3") (pin "1") (pinfunction "1_1") (pintype "input"))
      (node (ref "DT_PH_C4") (pin "1") (pinfunction "1_1") (pintype "unspecified"))
      (node (ref "DT_PH_C5") (pin "2") (pinfunction "2_2") (pintype "input"))
      (node (ref "DT_PH_C6") (pin "2") (pinfunction "2_2") (pintype "input"))
      (node (ref "DT_PH_R2") (pin "1") (pinfunction "1_1") (pintype "unspecified"))
      (node (ref "DT_PH_R4") (pin "1") (pinfunction "1_1") (pintype "unspecified"))
      (node (ref "DT_PRINTHEAD1") (pin "10") (pinfunction "GND_10") (pintype "unspecified"))
      (node (ref "DT_PRINTHEAD1") (pin "2") (pinfunction "GNDH_2") (pintype "unspecified"))
      (node (ref "DT_PRINTHEAD1") (pin "5") (pinfunction "GNDL_5") (pintype "unspecified"))
      (node (ref "DT_S1") (pin "2") (pinfunction "GND_2") (pintype "unspecified"))
      (node (ref "DT_S_R2") (pin "2") (pinfunction "2_2") (pintype "unspecified"))
      (node (ref "H6") (pin "4") (pinfunction "GND_4") (pintype "unspecified"))
      (node (ref "H8") (pin "6") (pinfunction "GND_6") (pintype "unspecified"))
      (node (ref "H8") (pin "7") (pinfunction "GND_7") (pintype "unspecified"))
      (node (ref "LIMIT_L1") (pin "2") (pinfunction "GND_2") (pintype "unspecified"))
      (node (ref "LIMIT_R1") (pin "2") (pinfunction "GND_2") (pintype "unspecified"))
      (node (ref "LINEAR_L1") (pin "1") (pinfunction "1_1") (pintype "unspecified"))
      (node (ref "LINEAR_L1") (pin "7") (pinfunction "7_7") (pintype "unspecified"))
      (node (ref "LINEAR_M_C1") (pin "2") (pinfunction "2_2") (pintype "unspecified"))
      (node (ref "MEGA-IOREF1") (pin "6") (pinfunction "GND_6") (pintype "unspecified"))
      (node (ref "MEGA-IOREF1") (pin "7") (pinfunction "GND_7") (pintype "unspecified"))
      (node (ref "MEGA-SCL2") (pin "4") (pinfunction "GND_4") (pintype "unspecified"))
      (node (ref "MOTOR_POWER1") (pin "2") (pinfunction "GND_2") (pintype "unspecified"))
      (node (ref "OXI_L1") (pin "1") (pinfunction "1_1") (pintype "unspecified"))
      (node (ref "OXI_L1") (pin "7") (pinfunction "7_7") (pintype "unspecified"))
      (node (ref "OXI_M_C1") (pin "2") (pinfunction "2_2") (pintype "unspecified"))
      (node (ref "Q2") (pin "3") (pinfunction "E_3") (pintype "input"))
      (node (ref "U29") (pin "2") (pinfunction "2_2") (pintype "unspecified"))
      (node (ref "U30") (pin "1") (pinfunction "1_1") (pintype "unspecified"))
      (node (ref "U5") (pin "18") (pinfunction "GND_18") (pintype "unspecified"))
      (node (ref "U7") (pin "1") (pinfunction "GND_1") (pintype "unspecified"))
      (node (ref "WASH_L1") (pin "1") (pinfunction "GND_1") (pintype "unspecified"))
      (node (ref "WASH_L1") (pin "7") (pinfunction "GND_7") (pintype "unspecified"))
      (node (ref "WASH_M_C1") (pin "2") (pinfunction "2_2") (pintype "unspecified"))
      (node (ref "WASTE1_L") (pin "1") (pinfunction "1_1") (pintype "unspecified"))
      (node (ref "WASTE1_L") (pin "7") (pinfunction "7_7") (pintype "unspecified"))
      (node (ref "WASTE1_R") (pin "1") (pinfunction "1_1") (pintype "unspecified"))
      (node (ref "WASTE2_L") (pin "1") (pinfunction "1_1") (pintype "unspecified"))
      (node (ref "WASTE2_L") (pin "7") (pinfunction "7_7") (pintype "unspecified"))
      (node (ref "WASTE2_R") (pin "1") (pinfunction "1_1") (pintype "unspecified"))
      (node (ref "WASTE_M_C1") (pin "2") (pinfunction "2_2") (pintype "unspecified"))
      (node (ref "WASTE_M_C2") (pin "2") (pinfunction "2_2") (pintype "unspecified"))
    )
    (net (code "20") (name "LIMIT_L_S") (class "Default")
      (node (ref "LIMIT_L1") (pin "3") (pinfunction "S_3") (pintype "unspecified"))
      (node (ref "U30") (pin "2") (pinfunction "2_2") (pintype "unspecified"))
    )
    (net (code "21") (name "LIMIT_R_S") (class "Default")
      (node (ref "LIMIT_R1") (pin "3") (pinfunction "S_3") (pintype "unspecified"))
      (node (ref "U29") (pin "1") (pinfunction "1_1") (pintype "unspecified"))
    )
    (net (code "22") (name "M_35V") (class "Default")
      (node (ref "ACT_L1") (pin "8") (pinfunction "VMOT_8") (pintype "unspecified"))
      (node (ref "ACT_M_C1") (pin "1") (pinfunction "1_1") (pintype "unspecified"))
      (node (ref "DA_L1") (pin "8") (pinfunction "8_8") (pintype "unspecified"))
      (node (ref "DA_M_C1") (pin "1") (pinfunction "1_1") (pintype "unspecified"))
      (node (ref "DC_L1") (pin "8") (pinfunction "8_8") (pintype "unspecified"))
      (node (ref "DC_M_C1") (pin "1") (pinfunction "1_1") (pintype "unspecified"))
      (node (ref "DET_L1") (pin "8") (pinfunction "8_8") (pintype "unspecified"))
      (node (ref "DET_M_C1") (pin "1") (pinfunction "1_1") (pintype "unspecified"))
      (node (ref "DG_L1") (pin "8") (pinfunction "8_8") (pintype "unspecified"))
      (node (ref "DG_M_C1") (pin "1") (pinfunction "1_1") (pintype "unspecified"))
      (node (ref "DT_L1") (pin "8") (pinfunction "8_8") (pintype "unspecified"))
      (node (ref "DT_M_C1") (pin "1") (pinfunction "1_1") (pintype "unspecified"))
      (node (ref "LINEAR_L1") (pin "8") (pinfunction "8_8") (pintype "unspecified"))
      (node (ref "LINEAR_M_C1") (pin "1") (pinfunction "1_1") (pintype "unspecified"))
      (node (ref "OXI_L1") (pin "8") (pinfunction "8_8") (pintype "unspecified"))
      (node (ref "OXI_M_C1") (pin "1") (pinfunction "1_1") (pintype "unspecified"))
      (node (ref "WASH_L1") (pin "8") (pinfunction "VMOT_8") (pintype "unspecified"))
      (node (ref "WASH_M_C1") (pin "1") (pinfunction "1_1") (pintype "unspecified"))
      (node (ref "WASTE1_L") (pin "8") (pinfunction "8_8") (pintype "unspecified"))
      (node (ref "WASTE2_L") (pin "8") (pinfunction "8_8") (pintype "unspecified"))
      (node (ref "WASTE_M_C1") (pin "1") (pinfunction "1_1") (pintype "unspecified"))
      (node (ref "WASTE_M_C2") (pin "1") (pinfunction "1_1") (pintype "unspecified"))
    )
    (net (code "23") (name "Net-(12V_POWER-12V)") (class "Default")
      (node (ref "12V_POWER") (pin "1") (pinfunction "12V_1") (pintype "unspecified"))
      (node (ref "D4") (pin "2") (pinfunction "A_2") (pintype "unspecified"))
    )
    (net (code "24") (name "Net-(ACT_L1-A1)") (class "Default")
      (node (ref "ACT_L1") (pin "4") (pinfunction "A1_4") (pintype "unspecified"))
      (node (ref "ACT_M1") (pin "3") (pinfunction "3_3") (pintype "unspecified"))
    )
    (net (code "25") (name "Net-(ACT_L1-A2)") (class "Default")
      (node (ref "ACT_L1") (pin "5") (pinfunction "A2_5") (pintype "unspecified"))
      (node (ref "ACT_M1") (pin "2") (pinfunction "2_2") (pintype "unspecified"))
    )
    (net (code "26") (name "Net-(ACT_L1-B1)") (class "Default")
      (node (ref "ACT_L1") (pin "3") (pinfunction "B1_3") (pintype "unspecified"))
      (node (ref "ACT_M1") (pin "4") (pinfunction "4_4") (pintype "unspecified"))
    )
    (net (code "27") (name "Net-(ACT_L1-B2)") (class "Default")
      (node (ref "ACT_L1") (pin "6") (pinfunction "B2_6") (pintype "unspecified"))
      (node (ref "ACT_M1") (pin "1") (pinfunction "1_1") (pintype "unspecified"))
    )
    (net (code "28") (name "Net-(ACT_PH_D1-K)") (class "Default")
      (node (ref "ACT_PH_C1") (pin "1") (pinfunction "1_1") (pintype "input"))
      (node (ref "ACT_PH_C2") (pin "1") (pinfunction "1_1") (pintype "unspecified"))
      (node (ref "ACT_PH_C3") (pin "2") (pinfunction "2_2") (pintype "input"))
      (node (ref "ACT_PH_C4") (pin "2") (pinfunction "2_2") (pintype "unspecified"))
      (node (ref "ACT_PH_D1") (pin "1") (pinfunction "K_1") (pintype "unspecified"))
      (node (ref "ACT_PH_M1") (pin "3") (pinfunction "S_3") (pintype "unspecified"))
      (node (ref "ACT_PH_R1") (pin "1") (pinfunction "1_1") (pintype "unspecified"))
      (node (ref "ACT_PH_ZD1") (pin "1") (pinfunction "1_1") (pintype "unspecified"))
    )
    (net (code "29") (name "Net-(ACT_PH_D2-K)") (class "Default")
      (node (ref "ACT_PH_C5") (pin "1") (pinfunction "1_1") (pintype "input"))
      (node (ref "ACT_PH_D2") (pin "1") (pinfunction "K_1") (pintype "unspecified"))
      (node (ref "ACT_PH_M2") (pin "3") (pinfunction "S_3") (pintype "unspecified"))
      (node (ref "ACT_PH_R3") (pin "1") (pinfunction "1_1") (pintype "unspecified"))
      (node (ref "ACT_PH_ZD2") (pin "1") (pinfunction "1_1") (pintype "unspecified"))
    )
    (net (code "30") (name "Net-(ACT_PH_M1-G)") (class "Default")
      (node (ref "ACT_PH_M1") (pin "1") (pinfunction "G_1") (pintype "unspecified"))
      (node (ref "ACT_PH_R1") (pin "2") (pinfunction "2_2") (pintype "unspecified"))
      (node (ref "ACT_PH_T1") (pin "1") (pinfunction "C_1") (pintype "unspecified"))
      (node (ref "ACT_PH_ZD1") (pin "2") (pinfunction "2_2") (pintype "unspecified"))
    )
    (net (code "31") (name "Net-(ACT_PH_M2-G)") (class "Default")
      (node (ref "ACT_PH_M2") (pin "1") (pinfunction "G_1") (pintype "unspecified"))
      (node (ref "ACT_PH_R3") (pin "2") (pinfunction "2_2") (pintype "unspecified"))
      (node (ref "ACT_PH_T2") (pin "1") (pinfunction "C_1") (pintype "unspecified"))
      (node (ref "ACT_PH_ZD2") (pin "2") (pinfunction "2_2") (pintype "unspecified"))
    )
    (net (code "32") (name "Net-(ACT_PH_T1-E)") (class "Default")
      (node (ref "ACT_PH_R2") (pin "2") (pinfunction "2_2") (pintype "unspecified"))
      (node (ref "ACT_PH_T1") (pin "3") (pinfunction "E_3") (pintype "unspecified"))
    )
    (net (code "33") (name "Net-(ACT_PH_T2-E)") (class "Default")
      (node (ref "ACT_PH_R4") (pin "2") (pinfunction "2_2") (pintype "unspecified"))
      (node (ref "ACT_PH_T2") (pin "3") (pinfunction "E_3") (pintype "unspecified"))
    )
    (net (code "34") (name "Net-(ACT_R1-Pad3)") (class "Default")
      (node (ref "ACT_R1") (pin "3") (pinfunction "3_3") (pintype "unspecified"))
      (node (ref "ACT_R1") (pin "4") (pinfunction "4_4") (pintype "unspecified"))
    )
    (net (code "35") (name "Net-(ACT_R1-Pad5)") (class "Default")
      (node (ref "ACT_R1") (pin "5") (pinfunction "5_5") (pintype "unspecified"))
      (node (ref "H5") (pin "1") (pinfunction "1_1") (pintype "unspecified"))
    )
    (net (code "36") (name "Net-(ACT_R1-Pad6)") (class "Default")
      (node (ref "ACT_R1") (pin "6") (pinfunction "6_6") (pintype "unspecified"))
      (node (ref "H5") (pin "3") (pinfunction "3_3") (pintype "unspecified"))
    )
    (net (code "37") (name "Net-(ACT_R1-Pad7)") (class "Default")
      (node (ref "ACT_R1") (pin "7") (pinfunction "7_7") (pintype "unspecified"))
      (node (ref "H5") (pin "5") (pinfunction "5_5") (pintype "unspecified"))
    )
    (net (code "38") (name "Net-(ACT_S1-S)") (class "Default")
      (node (ref "ACT_S1") (pin "3") (pinfunction "S_3") (pintype "unspecified"))
      (node (ref "ACT_S_R1") (pin "1") (pinfunction "1_1") (pintype "unspecified"))
    )
    (net (code "39") (name "Net-(D5-A)") (class "Default")
      (node (ref "D5") (pin "2") (pinfunction "A_2") (pintype "unspecified"))
      (node (ref "MOTOR_POWER1") (pin "1") (pinfunction "24V_1") (pintype "unspecified"))
    )
    (net (code "40") (name "Net-(DA_L1-Pad3)") (class "Default")
      (node (ref "DA_L1") (pin "3") (pinfunction "3_3") (pintype "unspecified"))
      (node (ref "DA_M1") (pin "4") (pinfunction "4_4") (pintype "unspecified"))
    )
    (net (code "41") (name "Net-(DA_L1-Pad4)") (class "Default")
      (node (ref "DA_L1") (pin "4") (pinfunction "4_4") (pintype "unspecified"))
      (node (ref "DA_M1") (pin "3") (pinfunction "3_3") (pintype "unspecified"))
    )
    (net (code "42") (name "Net-(DA_L1-Pad5)") (class "Default")
      (node (ref "DA_L1") (pin "5") (pinfunction "5_5") (pintype "unspecified"))
      (node (ref "DA_M1") (pin "2") (pinfunction "2_2") (pintype "unspecified"))
    )
    (net (code "43") (name "Net-(DA_L1-Pad6)") (class "Default")
      (node (ref "DA_L1") (pin "6") (pinfunction "6_6") (pintype "unspecified"))
      (node (ref "DA_M1") (pin "1") (pinfunction "1_1") (pintype "unspecified"))
    )
    (net (code "44") (name "Net-(DA_PH_D1-K)") (class "Default")
      (node (ref "DA_PH_C1") (pin "1") (pinfunction "1_1") (pintype "input"))
      (node (ref "DA_PH_C2") (pin "1") (pinfunction "1_1") (pintype "unspecified"))
      (node (ref "DA_PH_C3") (pin "2") (pinfunction "2_2") (pintype "input"))
      (node (ref "DA_PH_C4") (pin "2") (pinfunction "2_2") (pintype "unspecified"))
      (node (ref "DA_PH_D1") (pin "1") (pinfunction "K_1") (pintype "unspecified"))
      (node (ref "DA_PH_M1") (pin "3") (pinfunction "S_3") (pintype "unspecified"))
      (node (ref "DA_PH_R1") (pin "1") (pinfunction "1_1") (pintype "unspecified"))
      (node (ref "DA_PH_ZD1") (pin "1") (pinfunction "1_1") (pintype "unspecified"))
    )
    (net (code "45") (name "Net-(DA_PH_D2-K)") (class "Default")
      (node (ref "DA_PH_C5") (pin "1") (pinfunction "1_1") (pintype "input"))
      (node (ref "DA_PH_D2") (pin "1") (pinfunction "K_1") (pintype "unspecified"))
      (node (ref "DA_PH_M2") (pin "3") (pinfunction "S_3") (pintype "unspecified"))
      (node (ref "DA_PH_R3") (pin "1") (pinfunction "1_1") (pintype "unspecified"))
      (node (ref "DA_PH_ZD2") (pin "1") (pinfunction "1_1") (pintype "unspecified"))
    )
    (net (code "46") (name "Net-(DA_PH_M1-G)") (class "Default")
      (node (ref "DA_PH_M1") (pin "1") (pinfunction "G_1") (pintype "unspecified"))
      (node (ref "DA_PH_R1") (pin "2") (pinfunction "2_2") (pintype "unspecified"))
      (node (ref "DA_PH_T1") (pin "1") (pinfunction "C_1") (pintype "unspecified"))
      (node (ref "DA_PH_ZD1") (pin "2") (pinfunction "2_2") (pintype "unspecified"))
    )
    (net (code "47") (name "Net-(DA_PH_M2-G)") (class "Default")
      (node (ref "DA_PH_M2") (pin "1") (pinfunction "G_1") (pintype "unspecified"))
      (node (ref "DA_PH_R3") (pin "2") (pinfunction "2_2") (pintype "unspecified"))
      (node (ref "DA_PH_T2") (pin "1") (pinfunction "C_1") (pintype "unspecified"))
      (node (ref "DA_PH_ZD2") (pin "2") (pinfunction "2_2") (pintype "unspecified"))
    )
    (net (code "48") (name "Net-(DA_PH_T1-E)") (class "Default")
      (node (ref "DA_PH_R2") (pin "2") (pinfunction "2_2") (pintype "unspecified"))
      (node (ref "DA_PH_T1") (pin "3") (pinfunction "E_3") (pintype "unspecified"))
    )
    (net (code "49") (name "Net-(DA_PH_T2-E)") (class "Default")
      (node (ref "DA_PH_R4") (pin "2") (pinfunction "2_2") (pintype "unspecified"))
      (node (ref "DA_PH_T2") (pin "3") (pinfunction "E_3") (pintype "unspecified"))
    )
    (net (code "50") (name "Net-(DA_R1-Pad3)") (class "Default")
      (node (ref "DA_R1") (pin "3") (pinfunction "3_3") (pintype "unspecified"))
      (node (ref "DA_R1") (pin "4") (pinfunction "4_4") (pintype "unspecified"))
    )
    (net (code "51") (name "Net-(DA_R1-Pad5)") (class "Default")
      (node (ref "DA_R1") (pin "5") (pinfunction "5_5") (pintype "unspecified"))
      (node (ref "H1") (pin "1") (pinfunction "1_1") (pintype "unspecified"))
    )
    (net (code "52") (name "Net-(DA_R1-Pad6)") (class "Default")
      (node (ref "DA_R1") (pin "6") (pinfunction "6_6") (pintype "unspecified"))
      (node (ref "H1") (pin "3") (pinfunction "3_3") (pintype "unspecified"))
    )
    (net (code "53") (name "Net-(DA_R1-Pad7)") (class "Default")
      (node (ref "DA_R1") (pin "7") (pinfunction "7_7") (pintype "unspecified"))
      (node (ref "H1") (pin "5") (pinfunction "5_5") (pintype "unspecified"))
    )
    (net (code "54") (name "Net-(DA_S1-S)") (class "Default")
      (node (ref "DA_S1") (pin "3") (pinfunction "S_3") (pintype "unspecified"))
      (node (ref "DA_S_R1") (pin "1") (pinfunction "1_1") (pintype "unspecified"))
    )
    (net (code "55") (name "Net-(DC_L1-Pad3)") (class "Default")
      (node (ref "DC_L1") (pin "3") (pinfunction "3_3") (pintype "unspecified"))
      (node (ref "DC_M1") (pin "4") (pinfunction "4_4") (pintype "unspecified"))
    )
    (net (code "56") (name "Net-(DC_L1-Pad4)") (class "Default")
      (node (ref "DC_L1") (pin "4") (pinfunction "4_4") (pintype "unspecified"))
      (node (ref "DC_M1") (pin "3") (pinfunction "3_3") (pintype "unspecified"))
    )
    (net (code "57") (name "Net-(DC_L1-Pad5)") (class "Default")
      (node (ref "DC_L1") (pin "5") (pinfunction "5_5") (pintype "unspecified"))
      (node (ref "DC_M1") (pin "2") (pinfunction "2_2") (pintype "unspecified"))
    )
    (net (code "58") (name "Net-(DC_L1-Pad6)") (class "Default")
      (node (ref "DC_L1") (pin "6") (pinfunction "6_6") (pintype "unspecified"))
      (node (ref "DC_M1") (pin "1") (pinfunction "1_1") (pintype "unspecified"))
    )
    (net (code "59") (name "Net-(DC_PH_D1-K)") (class "Default")
      (node (ref "DC_PH_C2") (pin "1") (pinfunction "1_1") (pintype "unspecified"))
      (node (ref "DC_PH_C3") (pin "2") (pinfunction "2_2") (pintype "input"))
      (node (ref "DC_PH_C4") (pin "2") (pinfunction "2_2") (pintype "unspecified"))
      (node (ref "DC_PH_C7") (pin "1") (pinfunction "1_1") (pintype "input"))
      (node (ref "DC_PH_D1") (pin "1") (pinfunction "K_1") (pintype "unspecified"))
      (node (ref "DC_PH_M1") (pin "3") (pinfunction "S_3") (pintype "unspecified"))
      (node (ref "DC_PH_R1") (pin "1") (pinfunction "1_1") (pintype "unspecified"))
      (node (ref "DC_PH_ZD1") (pin "1") (pinfunction "1_1") (pintype "unspecified"))
    )
    (net (code "60") (name "Net-(DC_PH_D2-K)") (class "Default")
      (node (ref "DC_PH_C5") (pin "1") (pinfunction "1_1") (pintype "input"))
      (node (ref "DC_PH_D2") (pin "1") (pinfunction "K_1") (pintype "unspecified"))
      (node (ref "DC_PH_M2") (pin "3") (pinfunction "S_3") (pintype "unspecified"))
      (node (ref "DC_PH_R3") (pin "1") (pinfunction "1_1") (pintype "unspecified"))
      (node (ref "DC_PH_ZD2") (pin "1") (pinfunction "1_1") (pintype "unspecified"))
    )
    (net (code "61") (name "Net-(DC_PH_M1-G)") (class "Default")
      (node (ref "DC_PH_M1") (pin "1") (pinfunction "G_1") (pintype "unspecified"))
      (node (ref "DC_PH_R1") (pin "2") (pinfunction "2_2") (pintype "unspecified"))
      (node (ref "DC_PH_T1") (pin "1") (pinfunction "C_1") (pintype "unspecified"))
      (node (ref "DC_PH_ZD1") (pin "2") (pinfunction "2_2") (pintype "unspecified"))
    )
    (net (code "62") (name "Net-(DC_PH_M2-G)") (class "Default")
      (node (ref "DC_PH_M2") (pin "1") (pinfunction "G_1") (pintype "unspecified"))
      (node (ref "DC_PH_R3") (pin "2") (pinfunction "2_2") (pintype "unspecified"))
      (node (ref "DC_PH_T2") (pin "1") (pinfunction "C_1") (pintype "unspecified"))
      (node (ref "DC_PH_ZD2") (pin "2") (pinfunction "2_2") (pintype "unspecified"))
    )
    (net (code "63") (name "Net-(DC_PH_T1-E)") (class "Default")
      (node (ref "DC_PH_R2") (pin "2") (pinfunction "2_2") (pintype "unspecified"))
      (node (ref "DC_PH_T1") (pin "3") (pinfunction "E_3") (pintype "unspecified"))
    )
    (net (code "64") (name "Net-(DC_PH_T2-E)") (class "Default")
      (node (ref "DC_PH_R4") (pin "2") (pinfunction "2_2") (pintype "unspecified"))
      (node (ref "DC_PH_T2") (pin "3") (pinfunction "E_3") (pintype "unspecified"))
    )
    (net (code "65") (name "Net-(DC_R1-Pad3)") (class "Default")
      (node (ref "DC_R1") (pin "3") (pinfunction "3_3") (pintype "unspecified"))
      (node (ref "DC_R1") (pin "4") (pinfunction "4_4") (pintype "unspecified"))
    )
    (net (code "66") (name "Net-(DC_R1-Pad5)") (class "Default")
      (node (ref "DC_R1") (pin "5") (pinfunction "5_5") (pintype "unspecified"))
      (node (ref "H4") (pin "1") (pinfunction "1_1") (pintype "unspecified"))
    )
    (net (code "67") (name "Net-(DC_R1-Pad6)") (class "Default")
      (node (ref "DC_R1") (pin "6") (pinfunction "6_6") (pintype "unspecified"))
      (node (ref "H4") (pin "3") (pinfunction "3_3") (pintype "unspecified"))
    )
    (net (code "68") (name "Net-(DC_R1-Pad7)") (class "Default")
      (node (ref "DC_R1") (pin "7") (pinfunction "7_7") (pintype "unspecified"))
      (node (ref "H4") (pin "5") (pinfunction "5_5") (pintype "unspecified"))
    )
    (net (code "69") (name "Net-(DC_S1-S)") (class "Default")
      (node (ref "DC_S1") (pin "3") (pinfunction "S_3") (pintype "unspecified"))
      (node (ref "DC_S_R1") (pin "1") (pinfunction "1_1") (pintype "unspecified"))
    )
    (net (code "70") (name "Net-(DET_L1-Pad3)") (class "Default")
      (node (ref "DET_L1") (pin "3") (pinfunction "3_3") (pintype "unspecified"))
      (node (ref "DET_M1") (pin "4") (pinfunction "4_4") (pintype "unspecified"))
    )
    (net (code "71") (name "Net-(DET_L1-Pad4)") (class "Default")
      (node (ref "DET_L1") (pin "4") (pinfunction "4_4") (pintype "unspecified"))
      (node (ref "DET_M1") (pin "3") (pinfunction "3_3") (pintype "unspecified"))
    )
    (net (code "72") (name "Net-(DET_L1-Pad5)") (class "Default")
      (node (ref "DET_L1") (pin "5") (pinfunction "5_5") (pintype "unspecified"))
      (node (ref "DET_M1") (pin "2") (pinfunction "2_2") (pintype "unspecified"))
    )
    (net (code "73") (name "Net-(DET_L1-Pad6)") (class "Default")
      (node (ref "DET_L1") (pin "6") (pinfunction "6_6") (pintype "unspecified"))
      (node (ref "DET_M1") (pin "1") (pinfunction "1_1") (pintype "unspecified"))
    )
    (net (code "74") (name "Net-(DET_R1-Pad3)") (class "Default")
      (node (ref "DET_R1") (pin "3") (pinfunction "3_3") (pintype "unspecified"))
      (node (ref "DET_R1") (pin "4") (pinfunction "4_4") (pintype "unspecified"))
    )
    (net (code "75") (name "Net-(DET_R1-Pad5)") (class "Default")
      (node (ref "DET_R1") (pin "5") (pinfunction "5_5") (pintype "unspecified"))
      (node (ref "H18") (pin "1") (pinfunction "1_1") (pintype "unspecified"))
    )
    (net (code "76") (name "Net-(DET_R1-Pad6)") (class "Default")
      (node (ref "DET_R1") (pin "6") (pinfunction "6_6") (pintype "unspecified"))
      (node (ref "H18") (pin "3") (pinfunction "3_3") (pintype "unspecified"))
    )
    (net (code "77") (name "Net-(DET_R1-Pad7)") (class "Default")
      (node (ref "DET_R1") (pin "7") (pinfunction "7_7") (pintype "unspecified"))
      (node (ref "H18") (pin "5") (pinfunction "5_5") (pintype "unspecified"))
    )
    (net (code "78") (name "Net-(DG_L1-Pad3)") (class "Default")
      (node (ref "DG_L1") (pin "3") (pinfunction "3_3") (pintype "unspecified"))
      (node (ref "DG_M2") (pin "4") (pinfunction "4_4") (pintype "unspecified"))
    )
    (net (code "79") (name "Net-(DG_L1-Pad4)") (class "Default")
      (node (ref "DG_L1") (pin "4") (pinfunction "4_4") (pintype "unspecified"))
      (node (ref "DG_M2") (pin "3") (pinfunction "3_3") (pintype "unspecified"))
    )
    (net (code "80") (name "Net-(DG_L1-Pad5)") (class "Default")
      (node (ref "DG_L1") (pin "5") (pinfunction "5_5") (pintype "unspecified"))
      (node (ref "DG_M2") (pin "2") (pinfunction "2_2") (pintype "unspecified"))
    )
    (net (code "81") (name "Net-(DG_L1-Pad6)") (class "Default")
      (node (ref "DG_L1") (pin "6") (pinfunction "6_6") (pintype "unspecified"))
      (node (ref "DG_M2") (pin "1") (pinfunction "1_1") (pintype "unspecified"))
    )
    (net (code "82") (name "Net-(DG_PH_D1-K)") (class "Default")
      (node (ref "DG_PH_C1") (pin "1") (pinfunction "1_1") (pintype "input"))
      (node (ref "DG_PH_C2") (pin "1") (pinfunction "1_1") (pintype "unspecified"))
      (node (ref "DG_PH_C3") (pin "2") (pinfunction "2_2") (pintype "input"))
      (node (ref "DG_PH_C4") (pin "2") (pinfunction "2_2") (pintype "unspecified"))
      (node (ref "DG_PH_D1") (pin "1") (pinfunction "K_1") (pintype "unspecified"))
      (node (ref "DG_PH_M1") (pin "3") (pinfunction "S_3") (pintype "unspecified"))
      (node (ref "DG_PH_R1") (pin "1") (pinfunction "1_1") (pintype "unspecified"))
      (node (ref "DG_PH_ZD1") (pin "1") (pinfunction "1_1") (pintype "unspecified"))
    )
    (net (code "83") (name "Net-(DG_PH_D2-K)") (class "Default")
      (node (ref "DG_PH_C5") (pin "1") (pinfunction "1_1") (pintype "input"))
      (node (ref "DG_PH_D2") (pin "1") (pinfunction "K_1") (pintype "unspecified"))
      (node (ref "DG_PH_M2") (pin "3") (pinfunction "S_3") (pintype "unspecified"))
      (node (ref "DG_PH_R3") (pin "1") (pinfunction "1_1") (pintype "unspecified"))
      (node (ref "DG_PH_ZD2") (pin "1") (pinfunction "1_1") (pintype "unspecified"))
    )
    (net (code "84") (name "Net-(DG_PH_M1-G)") (class "Default")
      (node (ref "DG_PH_M1") (pin "1") (pinfunction "G_1") (pintype "unspecified"))
      (node (ref "DG_PH_R1") (pin "2") (pinfunction "2_2") (pintype "unspecified"))
      (node (ref "DG_PH_T1") (pin "1") (pinfunction "C_1") (pintype "unspecified"))
      (node (ref "DG_PH_ZD1") (pin "2") (pinfunction "2_2") (pintype "unspecified"))
    )
    (net (code "85") (name "Net-(DG_PH_M2-G)") (class "Default")
      (node (ref "DG_PH_M2") (pin "1") (pinfunction "G_1") (pintype "unspecified"))
      (node (ref "DG_PH_R3") (pin "2") (pinfunction "2_2") (pintype "unspecified"))
      (node (ref "DG_PH_T2") (pin "1") (pinfunction "C_1") (pintype "unspecified"))
      (node (ref "DG_PH_ZD2") (pin "2") (pinfunction "2_2") (pintype "unspecified"))
    )
    (net (code "86") (name "Net-(DG_PH_T1-E)") (class "Default")
      (node (ref "DG_PH_R2") (pin "2") (pinfunction "2_2") (pintype "unspecified"))
      (node (ref "DG_PH_T1") (pin "3") (pinfunction "E_3") (pintype "unspecified"))
    )
    (net (code "87") (name "Net-(DG_PH_T2-E)") (class "Default")
      (node (ref "DG_PH_R4") (pin "2") (pinfunction "2_2") (pintype "unspecified"))
      (node (ref "DG_PH_T2") (pin "3") (pinfunction "E_3") (pintype "unspecified"))
    )
    (net (code "88") (name "Net-(DG_R1-Pad3)") (class "Default")
      (node (ref "DG_R1") (pin "3") (pinfunction "3_3") (pintype "unspecified"))
      (node (ref "DG_R1") (pin "4") (pinfunction "4_4") (pintype "unspecified"))
    )
    (net (code "89") (name "Net-(DG_R1-Pad5)") (class "Default")
      (node (ref "DG_R1") (pin "5") (pinfunction "5_5") (pintype "unspecified"))
      (node (ref "H3") (pin "1") (pinfunction "1_1") (pintype "unspecified"))
    )
    (net (code "90") (name "Net-(DG_R1-Pad6)") (class "Default")
      (node (ref "DG_R1") (pin "6") (pinfunction "6_6") (pintype "unspecified"))
      (node (ref "H3") (pin "3") (pinfunction "3_3") (pintype "unspecified"))
    )
    (net (code "91") (name "Net-(DG_R1-Pad7)") (class "Default")
      (node (ref "DG_R1") (pin "7") (pinfunction "7_7") (pintype "unspecified"))
      (node (ref "H3") (pin "5") (pinfunction "5_5") (pintype "unspecified"))
    )
    (net (code "92") (name "Net-(DG_S1-S)") (class "Default")
      (node (ref "DG_S1") (pin "3") (pinfunction "S_3") (pintype "unspecified"))
      (node (ref "DG_S_R1") (pin "1") (pinfunction "1_1") (pintype "unspecified"))
    )
    (net (code "93") (name "Net-(DT_L1-Pad3)") (class "Default")
      (node (ref "DT_L1") (pin "3") (pinfunction "3_3") (pintype "unspecified"))
      (node (ref "DT_M2") (pin "4") (pinfunction "4_4") (pintype "unspecified"))
    )
    (net (code "94") (name "Net-(DT_L1-Pad4)") (class "Default")
      (node (ref "DT_L1") (pin "4") (pinfunction "4_4") (pintype "unspecified"))
      (node (ref "DT_M2") (pin "3") (pinfunction "3_3") (pintype "unspecified"))
    )
    (net (code "95") (name "Net-(DT_L1-Pad5)") (class "Default")
      (node (ref "DT_L1") (pin "5") (pinfunction "5_5") (pintype "unspecified"))
      (node (ref "DT_M2") (pin "2") (pinfunction "2_2") (pintype "unspecified"))
    )
    (net (code "96") (name "Net-(DT_L1-Pad6)") (class "Default")
      (node (ref "DT_L1") (pin "6") (pinfunction "6_6") (pintype "unspecified"))
      (node (ref "DT_M2") (pin "1") (pinfunction "1_1") (pintype "unspecified"))
    )
    (net (code "97") (name "Net-(DT_PH_D1-K)") (class "Default")
      (node (ref "DT_PH_C1") (pin "1") (pinfunction "1_1") (pintype "input"))
      (node (ref "DT_PH_C2") (pin "1") (pinfunction "1_1") (pintype "unspecified"))
      (node (ref "DT_PH_C3") (pin "2") (pinfunction "2_2") (pintype "input"))
      (node (ref "DT_PH_C4") (pin "2") (pinfunction "2_2") (pintype "unspecified"))
      (node (ref "DT_PH_D1") (pin "1") (pinfunction "K_1") (pintype "unspecified"))
      (node (ref "DT_PH_M1") (pin "3") (pinfunction "S_3") (pintype "unspecified"))
      (node (ref "DT_PH_R1") (pin "1") (pinfunction "1_1") (pintype "unspecified"))
      (node (ref "DT_PH_ZD1") (pin "1") (pinfunction "1_1") (pintype "unspecified"))
    )
    (net (code "98") (name "Net-(DT_PH_D2-K)") (class "Default")
      (node (ref "DT_PH_C5") (pin "1") (pinfunction "1_1") (pintype "input"))
      (node (ref "DT_PH_D2") (pin "1") (pinfunction "K_1") (pintype "unspecified"))
      (node (ref "DT_PH_M2") (pin "3") (pinfunction "S_3") (pintype "unspecified"))
      (node (ref "DT_PH_R3") (pin "1") (pinfunction "1_1") (pintype "unspecified"))
      (node (ref "DT_PH_ZD2") (pin "1") (pinfunction "1_1") (pintype "unspecified"))
    )
    (net (code "99") (name "Net-(DT_PH_M1-G)") (class "Default")
      (node (ref "DT_PH_M1") (pin "1") (pinfunction "G_1") (pintype "unspecified"))
      (node (ref "DT_PH_R1") (pin "2") (pinfunction "2_2") (pintype "unspecified"))
      (node (ref "DT_PH_T1") (pin "1") (pinfunction "C_1") (pintype "unspecified"))
      (node (ref "DT_PH_ZD1") (pin "2") (pinfunction "2_2") (pintype "unspecified"))
    )
    (net (code "100") (name "Net-(DT_PH_M2-G)") (class "Default")
      (node (ref "DT_PH_M2") (pin "1") (pinfunction "G_1") (pintype "unspecified"))
      (node (ref "DT_PH_R3") (pin "2") (pinfunction "2_2") (pintype "unspecified"))
      (node (ref "DT_PH_T2") (pin "1") (pinfunction "C_1") (pintype "unspecified"))
      (node (ref "DT_PH_ZD2") (pin "2") (pinfunction "2_2") (pintype "unspecified"))
    )
    (net (code "101") (name "Net-(DT_PH_T1-E)") (class "Default")
      (node (ref "DT_PH_R2") (pin "2") (pinfunction "2_2") (pintype "unspecified"))
      (node (ref "DT_PH_T1") (pin "3") (pinfunction "E_3") (pintype "unspecified"))
    )
    (net (code "102") (name "Net-(DT_PH_T2-E)") (class "Default")
      (node (ref "DT_PH_R4") (pin "2") (pinfunction "2_2") (pintype "unspecified"))
      (node (ref "DT_PH_T2") (pin "3") (pinfunction "E_3") (pintype "unspecified"))
    )
    (net (code "103") (name "Net-(DT_R1-Pad3)") (class "Default")
      (node (ref "DT_R1") (pin "3") (pinfunction "3_3") (pintype "unspecified"))
      (node (ref "DT_R1") (pin "4") (pinfunction "4_4") (pintype "unspecified"))
    )
    (net (code "104") (name "Net-(DT_R1-Pad5)") (class "Default")
      (node (ref "DT_R1") (pin "5") (pinfunction "5_5") (pintype "unspecified"))
      (node (ref "H2") (pin "1") (pinfunction "1_1") (pintype "unspecified"))
    )
    (net (code "105") (name "Net-(DT_R1-Pad6)") (class "Default")
      (node (ref "DT_R1") (pin "6") (pinfunction "6_6") (pintype "unspecified"))
      (node (ref "H2") (pin "3") (pinfunction "3_3") (pintype "unspecified"))
    )
    (net (code "106") (name "Net-(DT_R1-Pad7)") (class "Default")
      (node (ref "DT_R1") (pin "7") (pinfunction "7_7") (pintype "unspecified"))
      (node (ref "H2") (pin "5") (pinfunction "5_5") (pintype "unspecified"))
    )
    (net (code "107") (name "Net-(DT_S1-S)") (class "Default")
      (node (ref "DT_S1") (pin "3") (pinfunction "S_3") (pintype "unspecified"))
      (node (ref "DT_S_R1") (pin "1") (pinfunction "1_1") (pintype "unspecified"))
    )
    (net (code "108") (name "Net-(H8-5V)") (class "Default")
      (node (ref "H8") (pin "5") (pinfunction "5V_5") (pintype "unspecified"))
      (node (ref "R2") (pin "1") (pinfunction "1_1") (pintype "unspecified"))
      (node (ref "SW1") (pin "3") (pinfunction "3_3") (pintype "unspecified"))
    )
    (net (code "109") (name "Net-(H8-RESET)") (class "Default")
      (node (ref "H8") (pin "3") (pinfunction "RESET_3") (pintype "unspecified"))
      (node (ref "SW1") (pin "1") (pinfunction "1_1") (pintype "unspecified"))
    )
    (net (code "110") (name "Net-(H14-Pad1)") (class "Default")
      (node (ref "H14") (pin "1") (pinfunction "1_1") (pintype "unspecified"))
      (node (ref "WASH_R1") (pin "5") (pinfunction "5_5") (pintype "unspecified"))
    )
    (net (code "111") (name "Net-(H14-Pad3)") (class "Default")
      (node (ref "H14") (pin "3") (pinfunction "3_3") (pintype "unspecified"))
      (node (ref "WASH_R1") (pin "6") (pinfunction "6_6") (pintype "unspecified"))
    )
    (net (code "112") (name "Net-(H14-Pad5)") (class "Default")
      (node (ref "H14") (pin "5") (pinfunction "5_5") (pintype "unspecified"))
      (node (ref "WASH_R1") (pin "7") (pinfunction "7_7") (pintype "unspecified"))
    )
    (net (code "113") (name "Net-(H15-Pad1)") (class "Default")
      (node (ref "H15") (pin "1") (pinfunction "1_1") (pintype "unspecified"))
      (node (ref "WASTE2_R") (pin "5") (pinfunction "5_5") (pintype "unspecified"))
    )
    (net (code "114") (name "Net-(H15-Pad3)") (class "Default")
      (node (ref "H15") (pin "3") (pinfunction "3_3") (pintype "unspecified"))
      (node (ref "WASTE2_R") (pin "6") (pinfunction "6_6") (pintype "unspecified"))
    )
    (net (code "115") (name "Net-(H15-Pad5)") (class "Default")
      (node (ref "H15") (pin "5") (pinfunction "5_5") (pintype "unspecified"))
      (node (ref "WASTE2_R") (pin "7") (pinfunction "7_7") (pintype "unspecified"))
    )
    (net (code "116") (name "Net-(H16-Pad1)") (class "Default")
      (node (ref "H16") (pin "1") (pinfunction "1_1") (pintype "unspecified"))
      (node (ref "WASTE1_R") (pin "5") (pinfunction "5_5") (pintype "unspecified"))
    )
    (net (code "117") (name "Net-(H16-Pad3)") (class "Default")
      (node (ref "H16") (pin "3") (pinfunction "3_3") (pintype "unspecified"))
      (node (ref "WASTE1_R") (pin "6") (pinfunction "6_6") (pintype "unspecified"))
    )
    (net (code "118") (name "Net-(H16-Pad5)") (class "Default")
      (node (ref "H16") (pin "5") (pinfunction "5_5") (pintype "unspecified"))
      (node (ref "WASTE1_R") (pin "7") (pinfunction "7_7") (pintype "unspecified"))
    )
    (net (code "119") (name "Net-(H17-Pad1)") (class "Default")
      (node (ref "H17") (pin "1") (pinfunction "1_1") (pintype "unspecified"))
      (node (ref "OXI_R1") (pin "5") (pinfunction "5_5") (pintype "unspecified"))
    )
    (net (code "120") (name "Net-(H17-Pad3)") (class "Default")
      (node (ref "H17") (pin "3") (pinfunction "3_3") (pintype "unspecified"))
      (node (ref "OXI_R1") (pin "6") (pinfunction "6_6") (pintype "unspecified"))
    )
    (net (code "121") (name "Net-(H17-Pad5)") (class "Default")
      (node (ref "H17") (pin "5") (pinfunction "5_5") (pintype "unspecified"))
      (node (ref "OXI_R1") (pin "7") (pinfunction "7_7") (pintype "unspecified"))
    )
    (net (code "122") (name "Net-(H19-Pad1)") (class "Default")
      (node (ref "H19") (pin "1") (pinfunction "1_1") (pintype "unspecified"))
      (node (ref "LINEAR_R1") (pin "5") (pinfunction "5_5") (pintype "unspecified"))
    )
    (net (code "123") (name "Net-(H19-Pad3)") (class "Default")
      (node (ref "H19") (pin "3") (pinfunction "3_3") (pintype "unspecified"))
      (node (ref "LINEAR_R1") (pin "6") (pinfunction "6_6") (pintype "unspecified"))
    )
    (net (code "124") (name "Net-(H19-Pad5)") (class "Default")
      (node (ref "H19") (pin "5") (pinfunction "5_5") (pintype "unspecified"))
      (node (ref "LINEAR_R1") (pin "7") (pinfunction "7_7") (pintype "unspecified"))
    )
    (net (code "125") (name "Net-(LINEAR_L1-Pad3)") (class "Default")
      (node (ref "LINEAR_L1") (pin "3") (pinfunction "3_3") (pintype "unspecified"))
      (node (ref "LINEAR_M1") (pin "4") (pinfunction "4_4") (pintype "unspecified"))
    )
    (net (code "126") (name "Net-(LINEAR_L1-Pad4)") (class "Default")
      (node (ref "LINEAR_L1") (pin "4") (pinfunction "4_4") (pintype "unspecified"))
      (node (ref "LINEAR_M1") (pin "3") (pinfunction "3_3") (pintype "unspecified"))
    )
    (net (code "127") (name "Net-(LINEAR_L1-Pad5)") (class "Default")
      (node (ref "LINEAR_L1") (pin "5") (pinfunction "5_5") (pintype "unspecified"))
      (node (ref "LINEAR_M1") (pin "2") (pinfunction "2_2") (pintype "unspecified"))
    )
    (net (code "128") (name "Net-(LINEAR_L1-Pad6)") (class "Default")
      (node (ref "LINEAR_L1") (pin "6") (pinfunction "6_6") (pintype "unspecified"))
      (node (ref "LINEAR_M1") (pin "1") (pinfunction "1_1") (pintype "unspecified"))
    )
    (net (code "129") (name "Net-(LINEAR_R1-Pad3)") (class "Default")
      (node (ref "LINEAR_R1") (pin "3") (pinfunction "3_3") (pintype "unspecified"))
      (node (ref "LINEAR_R1") (pin "4") (pinfunction "4_4") (pintype "unspecified"))
    )
    (net (code "130") (name "Net-(MEGA-IOREF1-5V)") (class "Default")
      (node (ref "MEGA-IOREF1") (pin "5") (pinfunction "5V_5") (pintype "unspecified"))
      (node (ref "SW3") (pin "2") (pinfunction "2_2") (pintype "unspecified"))
    )
    (net (code "131") (name "Net-(MEGA-IOREF1-RESET)") (class "Default")
      (node (ref "MEGA-IOREF1") (pin "3") (pinfunction "RESET_3") (pintype "unspecified"))
      (node (ref "SW3") (pin "4") (pinfunction "4_4") (pintype "unspecified"))
    )
    (net (code "132") (name "Net-(OXI_L1-Pad3)") (class "Default")
      (node (ref "OXI_L1") (pin "3") (pinfunction "3_3") (pintype "unspecified"))
      (node (ref "OXI_M1") (pin "4") (pinfunction "4_4") (pintype "unspecified"))
    )
    (net (code "133") (name "Net-(OXI_L1-Pad4)") (class "Default")
      (node (ref "OXI_L1") (pin "4") (pinfunction "4_4") (pintype "unspecified"))
      (node (ref "OXI_M1") (pin "3") (pinfunction "3_3") (pintype "unspecified"))
    )
    (net (code "134") (name "Net-(OXI_L1-Pad5)") (class "Default")
      (node (ref "OXI_L1") (pin "5") (pinfunction "5_5") (pintype "unspecified"))
      (node (ref "OXI_M1") (pin "2") (pinfunction "2_2") (pintype "unspecified"))
    )
    (net (code "135") (name "Net-(OXI_L1-Pad6)") (class "Default")
      (node (ref "OXI_L1") (pin "6") (pinfunction "6_6") (pintype "unspecified"))
      (node (ref "OXI_M1") (pin "1") (pinfunction "1_1") (pintype "unspecified"))
    )
    (net (code "136") (name "Net-(OXI_R1-Pad3)") (class "Default")
      (node (ref "OXI_R1") (pin "3") (pinfunction "3_3") (pintype "unspecified"))
      (node (ref "OXI_R1") (pin "4") (pinfunction "4_4") (pintype "unspecified"))
    )
    (net (code "137") (name "Net-(Q2-B)") (class "Default")
      (node (ref "Q2") (pin "1") (pinfunction "B_1") (pintype "input"))
      (node (ref "R6") (pin "1") (pinfunction "1_1") (pintype "unspecified"))
    )
    (net (code "138") (name "Net-(Q2-C)") (class "Default")
      (node (ref "D2") (pin "2") (pinfunction "2_2") (pintype "unspecified"))
      (node (ref "Q2") (pin "2") (pinfunction "C_2") (pintype "input"))
      (node (ref "U6") (pin "2") (pinfunction "GND_2") (pintype "unspecified"))
    )
    (net (code "139") (name "Net-(U5-none)") (class "Default")
      (node (ref "R1") (pin "2") (pinfunction "2_2") (pintype "unspecified"))
      (node (ref "U5") (pin "1") (pinfunction "none_1") (pintype "unspecified"))
    )
    (net (code "140") (name "Net-(WASH_L1-A1)") (class "Default")
      (node (ref "WASH_L1") (pin "4") (pinfunction "A1_4") (pintype "unspecified"))
      (node (ref "WASH_M1") (pin "3") (pinfunction "3_3") (pintype "unspecified"))
    )
    (net (code "141") (name "Net-(WASH_L1-A2)") (class "Default")
      (node (ref "WASH_L1") (pin "5") (pinfunction "A2_5") (pintype "unspecified"))
      (node (ref "WASH_M1") (pin "2") (pinfunction "2_2") (pintype "unspecified"))
    )
    (net (code "142") (name "Net-(WASH_L1-B1)") (class "Default")
      (node (ref "WASH_L1") (pin "3") (pinfunction "B1_3") (pintype "unspecified"))
      (node (ref "WASH_M1") (pin "4") (pinfunction "4_4") (pintype "unspecified"))
    )
    (net (code "143") (name "Net-(WASH_L1-B2)") (class "Default")
      (node (ref "WASH_L1") (pin "6") (pinfunction "B2_6") (pintype "unspecified"))
      (node (ref "WASH_M1") (pin "1") (pinfunction "1_1") (pintype "unspecified"))
    )
    (net (code "144") (name "Net-(WASH_R1-Pad3)") (class "Default")
      (node (ref "WASH_R1") (pin "3") (pinfunction "3_3") (pintype "unspecified"))
      (node (ref "WASH_R1") (pin "4") (pinfunction "4_4") (pintype "unspecified"))
    )
    (net (code "145") (name "Net-(WASTE1_L-Pad3)") (class "Default")
      (node (ref "WASTE1_L") (pin "3") (pinfunction "3_3") (pintype "unspecified"))
      (node (ref "WASTE1_M") (pin "4") (pinfunction "4_4") (pintype "unspecified"))
    )
    (net (code "146") (name "Net-(WASTE1_L-Pad4)") (class "Default")
      (node (ref "WASTE1_L") (pin "4") (pinfunction "4_4") (pintype "unspecified"))
      (node (ref "WASTE1_M") (pin "3") (pinfunction "3_3") (pintype "unspecified"))
    )
    (net (code "147") (name "Net-(WASTE1_L-Pad5)") (class "Default")
      (node (ref "WASTE1_L") (pin "5") (pinfunction "5_5") (pintype "unspecified"))
      (node (ref "WASTE1_M") (pin "2") (pinfunction "2_2") (pintype "unspecified"))
    )
    (net (code "148") (name "Net-(WASTE1_L-Pad6)") (class "Default")
      (node (ref "WASTE1_L") (pin "6") (pinfunction "6_6") (pintype "unspecified"))
      (node (ref "WASTE1_M") (pin "1") (pinfunction "1_1") (pintype "unspecified"))
    )
    (net (code "149") (name "Net-(WASTE1_R-Pad3)") (class "Default")
      (node (ref "WASTE1_R") (pin "3") (pinfunction "3_3") (pintype "unspecified"))
      (node (ref "WASTE1_R") (pin "4") (pinfunction "4_4") (pintype "unspecified"))
    )
    (net (code "150") (name "Net-(WASTE2_L-Pad3)") (class "Default")
      (node (ref "WASTE2_L") (pin "3") (pinfunction "3_3") (pintype "unspecified"))
      (node (ref "WASTE2_M") (pin "4") (pinfunction "4_4") (pintype "unspecified"))
    )
    (net (code "151") (name "Net-(WASTE2_L-Pad4)") (class "Default")
      (node (ref "WASTE2_L") (pin "4") (pinfunction "4_4") (pintype "unspecified"))
      (node (ref "WASTE2_M") (pin "3") (pinfunction "3_3") (pintype "unspecified"))
    )
    (net (code "152") (name "Net-(WASTE2_L-Pad5)") (class "Default")
      (node (ref "WASTE2_L") (pin "5") (pinfunction "5_5") (pintype "unspecified"))
      (node (ref "WASTE2_M") (pin "2") (pinfunction "2_2") (pintype "unspecified"))
    )
    (net (code "153") (name "Net-(WASTE2_L-Pad6)") (class "Default")
      (node (ref "WASTE2_L") (pin "6") (pinfunction "6_6") (pintype "unspecified"))
      (node (ref "WASTE2_M") (pin "1") (pinfunction "1_1") (pintype "unspecified"))
    )
    (net (code "154") (name "Net-(WASTE2_R-Pad3)") (class "Default")
      (node (ref "WASTE2_R") (pin "3") (pinfunction "3_3") (pintype "unspecified"))
      (node (ref "WASTE2_R") (pin "4") (pinfunction "4_4") (pintype "unspecified"))
    )
    (net (code "155") (name "OXI_E") (class "Default")
      (node (ref "MEGA-SCL2") (pin "10") (pinfunction "8_10") (pintype "unspecified"))
    )
    (net (code "156") (name "OXI_enable") (class "Default")
      (node (ref "OXI_R1") (pin "8") (pinfunction "8_8") (pintype "unspecified"))
    )
    (net (code "157") (name "OXI_pulse") (class "Default")
      (node (ref "MEGA-D1") (pin "6") (pinfunction "2_6") (pintype "unspecified"))
    )
    (net (code "158") (name "OXI_step") (class "Default")
      (node (ref "OXI_R1") (pin "2") (pinfunction "2_2") (pintype "unspecified"))
    )
    (net (code "159") (name "PH_35V") (class "Default")
      (node (ref "ACT_PH_D1") (pin "2") (pinfunction "A_2") (pintype "unspecified"))
      (node (ref "ACT_PH_D2") (pin "2") (pinfunction "A_2") (pintype "unspecified"))
      (node (ref "DA_PH_D1") (pin "2") (pinfunction "A_2") (pintype "unspecified"))
      (node (ref "DA_PH_D2") (pin "2") (pinfunction "A_2") (pintype "unspecified"))
      (node (ref "DC_PH_D1") (pin "2") (pinfunction "A_2") (pintype "unspecified"))
      (node (ref "DC_PH_D2") (pin "2") (pinfunction "A_2") (pintype "unspecified"))
      (node (ref "DG_PH_D1") (pin "2") (pinfunction "A_2") (pintype "unspecified"))
      (node (ref "DG_PH_D2") (pin "2") (pinfunction "A_2") (pintype "unspecified"))
      (node (ref "DT_PH_D1") (pin "2") (pinfunction "A_2") (pintype "unspecified"))
      (node (ref "DT_PH_D2") (pin "2") (pinfunction "A_2") (pintype "unspecified"))
    )
    (net (code "160") (name "PH_CLK") (class "Default")
      (node (ref "ACT_PRINTHEAD1") (pin "15") (pinfunction "CLK_15") (pintype "unspecified"))
      (node (ref "DA_PRINTHEAD1") (pin "15") (pinfunction "CLK_15") (pintype "unspecified"))
      (node (ref "DC_PRINTHEAD1") (pin "15") (pinfunction "CLK_15") (pintype "unspecified"))
      (node (ref "DG_PRINTHEAD1") (pin "15") (pinfunction "CLK_15") (pintype "unspecified"))
      (node (ref "DT_PRINTHEAD1") (pin "15") (pinfunction "CLK_15") (pintype "unspecified"))
      (node (ref "U5") (pin "16") (pinfunction "50_16") (pintype "unspecified"))
    )
    (net (code "161") (name "PH_MISO") (class "Default")
      (node (ref "ACT_PRINTHEAD1") (pin "13") (pinfunction "MISO_13") (pintype "unspecified"))
      (node (ref "DA_PRINTHEAD1") (pin "13") (pinfunction "MISO_13") (pintype "unspecified"))
      (node (ref "DC_PRINTHEAD1") (pin "13") (pinfunction "MISO_13") (pintype "unspecified"))
      (node (ref "DG_PRINTHEAD1") (pin "13") (pinfunction "MISO_13") (pintype "unspecified"))
      (node (ref "DT_PRINTHEAD1") (pin "13") (pinfunction "MISO_13") (pintype "unspecified"))
      (node (ref "U5") (pin "15") (pinfunction "48_15") (pintype "unspecified"))
    )
    (net (code "162") (name "PH_MOSI") (class "Default")
      (node (ref "ACT_PRINTHEAD1") (pin "8") (pinfunction "MOSI_8") (pintype "unspecified"))
      (node (ref "DA_PRINTHEAD1") (pin "8") (pinfunction "MOSI_8") (pintype "unspecified"))
      (node (ref "DC_PRINTHEAD1") (pin "8") (pinfunction "MOSI_8") (pintype "unspecified"))
      (node (ref "DG_PRINTHEAD1") (pin "8") (pinfunction "MOSI_8") (pintype "unspecified"))
      (node (ref "DT_PRINTHEAD1") (pin "8") (pinfunction "MOSI_8") (pintype "unspecified"))
      (node (ref "U7") (pin "4") (pinfunction "49_4") (pintype "unspecified"))
    )
    (net (code "163") (name "PH_SCK") (class "Default")
      (node (ref "ACT_PRINTHEAD1") (pin "11") (pinfunction "SCK_11") (pintype "unspecified"))
      (node (ref "DA_PRINTHEAD1") (pin "11") (pinfunction "SCK_11") (pintype "unspecified"))
      (node (ref "DC_PRINTHEAD1") (pin "11") (pinfunction "SCK_11") (pintype "unspecified"))
      (node (ref "DG_PRINTHEAD1") (pin "11") (pinfunction "SCK_11") (pintype "unspecified"))
      (node (ref "DT_PRINTHEAD1") (pin "11") (pinfunction "SCK_11") (pintype "unspecified"))
      (node (ref "U7") (pin "5") (pinfunction "47_5") (pintype "unspecified"))
    )
    (net (code "164") (name "PH_reset") (class "Default")
      (node (ref "ACT_PRINTHEAD1") (pin "7") (pinfunction "RESET_7") (pintype "unspecified"))
      (node (ref "DA_PRINTHEAD1") (pin "7") (pinfunction "RESET_7") (pintype "unspecified"))
      (node (ref "DC_PRINTHEAD1") (pin "7") (pinfunction "RESET_7") (pintype "unspecified"))
      (node (ref "DG_PRINTHEAD1") (pin "7") (pinfunction "RESET_7") (pintype "unspecified"))
      (node (ref "DT_PRINTHEAD1") (pin "7") (pinfunction "RESET_7") (pintype "unspecified"))
      (node (ref "U7") (pin "3") (pinfunction "51_3") (pintype "unspecified"))
    )
    (net (code "165") (name "RX") (class "Default")
      (node (ref "MEGA-D1") (pin "8") (pinfunction "0_8") (pintype "unspecified"))
    )
    (net (code "166") (name "SCL") (class "Default")
      (node (ref "H9") (pin "6") (pinfunction "A5_6") (pintype "input"))
      (node (ref "MEGA-D2") (pin "8") (pinfunction "21_8") (pintype "unspecified"))
    )
    (net (code "167") (name "SDA") (class "Default")
      (node (ref "H9") (pin "5") (pinfunction "A4_5") (pintype "input"))
      (node (ref "MEGA-D2") (pin "7") (pinfunction "20_7") (pintype "unspecified"))
    )
    (net (code "168") (name "TX") (class "Default")
      (node (ref "MEGA-D1") (pin "7") (pinfunction "1_7") (pintype "unspecified"))
    )
    (net (code "169") (name "bulk_RX") (class "Default")
      (node (ref "MEGA-D2") (pin "6") (pinfunction "19_6") (pintype "unspecified"))
    )
    (net (code "170") (name "bulk_TX") (class "Default")
      (node (ref "MEGA-D2") (pin "5") (pinfunction "18_5") (pintype "unspecified"))
    )
    (net (code "171") (name "bulk_direction") (class "Default")
      (node (ref "DET_R1") (pin "1") (pinfunction "1_1") (pintype "unspecified"))
      (node (ref "OXI_R1") (pin "1") (pinfunction "1_1") (pintype "unspecified"))
      (node (ref "WASH_R1") (pin "1") (pinfunction "1_1") (pintype "unspecified"))
    )
    (net (code "172") (name "dA_PH_VPPH") (class "Default")
      (node (ref "DA_PH_M2") (pin "2") (pinfunction "D_2") (pintype "unspecified"))
      (node (ref "DA_PRINTHEAD1") (pin "3") (pinfunction "VPPH_3") (pintype "unspecified"))
    )
    (net (code "173") (name "dA_PH_VPPL") (class "Default")
      (node (ref "DA_PH_M1") (pin "2") (pinfunction "D_2") (pintype "unspecified"))
      (node (ref "DA_PRINTHEAD1") (pin "4") (pinfunction "VPPL_4") (pintype "unspecified"))
    )
    (net (code "174") (name "dA_PH_fault") (class "Default")
      (node (ref "DA_PRINTHEAD1") (pin "6") (pinfunction "FAULT_6") (pintype "unspecified"))
      (node (ref "U7") (pin "14") (pinfunction "29_14") (pintype "unspecified"))
    )
    (net (code "175") (name "dA_PH_fire") (class "Default")
      (node (ref "DA_PRINTHEAD1") (pin "16") (pinfunction "FIRE_16") (pintype "unspecified"))
      (node (ref "U5") (pin "6") (pinfunction "30_6") (pintype "unspecified"))
    )
    (net (code "176") (name "dA_PH_nSS1") (class "Default")
      (node (ref "DA_PRINTHEAD1") (pin "12") (pinfunction "nSS1_12") (pintype "unspecified"))
      (node (ref "U7") (pin "15") (pinfunction "27_15") (pintype "unspecified"))
    )
    (net (code "177") (name "dA_PH_nSS2") (class "Default")
      (node (ref "DA_PRINTHEAD1") (pin "1") (pinfunction "nSS2_1") (pintype "unspecified"))
      (node (ref "U5") (pin "5") (pinfunction "28_5") (pintype "unspecified"))
    )
    (net (code "178") (name "dA_PH_ready") (class "Default")
      (node (ref "DA_PRINTHEAD1") (pin "14") (pinfunction "READY_14") (pintype "unspecified"))
      (node (ref "U7") (pin "13") (pinfunction "31_13") (pintype "unspecified"))
    )
    (net (code "179") (name "dA_S") (class "Default")
      (node (ref "DA_S_R1") (pin "2") (pinfunction "2_2") (pintype "unspecified"))
      (node (ref "DA_S_R2") (pin "1") (pinfunction "1_1") (pintype "unspecified"))
      (node (ref "H9") (pin "2") (pinfunction "A1_2") (pintype "input"))
    )
    (net (code "180") (name "dA_enable") (class "Default")
      (node (ref "DA_R1") (pin "8") (pinfunction "8_8") (pintype "unspecified"))
      (node (ref "H7") (pin "7") (pinfunction "1_7") (pintype "unspecified"))
    )
    (net (code "181") (name "dA_step") (class "Default")
      (node (ref "DA_R1") (pin "2") (pinfunction "2_2") (pintype "unspecified"))
      (node (ref "H7") (pin "2") (pinfunction "6_2") (pintype "unspecified"))
    )
    (net (code "182") (name "dC_PH_VPPH") (class "Default")
      (node (ref "DC_PH_M2") (pin "2") (pinfunction "D_2") (pintype "unspecified"))
      (node (ref "DC_PRINTHEAD1") (pin "3") (pinfunction "VPPH_3") (pintype "unspecified"))
    )
    (net (code "183") (name "dC_PH_VPPL") (class "Default")
      (node (ref "DC_PH_M1") (pin "2") (pinfunction "D_2") (pintype "unspecified"))
      (node (ref "DC_PRINTHEAD1") (pin "4") (pinfunction "VPPL_4") (pintype "unspecified"))
    )
    (net (code "184") (name "dC_PH_fault") (class "Default")
      (node (ref "DC_PRINTHEAD1") (pin "6") (pinfunction "FAULT_6") (pintype "unspecified"))
      (node (ref "U5") (pin "13") (pinfunction "44_13") (pintype "unspecified"))
    )
    (net (code "185") (name "dC_PH_fire") (class "Default")
      (node (ref "DC_PRINTHEAD1") (pin "16") (pinfunction "FIRE_16") (pintype "unspecified"))
      (node (ref "U7") (pin "6") (pinfunction "45_6") (pintype "unspecified"))
    )
    (net (code "186") (name "dC_PH_nSS1") (class "Default")
      (node (ref "DC_PRINTHEAD1") (pin "12") (pinfunction "nSS1_12") (pintype "unspecified"))
      (node (ref "U5") (pin "12") (pinfunction "42_12") (pintype "unspecified"))
    )
    (net (code "187") (name "dC_PH_nSS2") (class "Default")
      (node (ref "DC_PRINTHEAD1") (pin "1") (pinfunction "nSS2_1") (pintype "unspecified"))
      (node (ref "U7") (pin "7") (pinfunction "43_7") (pintype "unspecified"))
    )
    (net (code "188") (name "dC_PH_ready") (class "Default")
      (node (ref "DC_PRINTHEAD1") (pin "14") (pinfunction "READY_14") (pintype "unspecified"))
      (node (ref "U5") (pin "14") (pinfunction "46_14") (pintype "unspecified"))
    )
    (net (code "189") (name "dC_S") (class "Default")
      (node (ref "DC_S_R1") (pin "2") (pinfunction "2_2") (pintype "unspecified"))
      (node (ref "DC_S_R2") (pin "1") (pinfunction "1_1") (pintype "unspecified"))
      (node (ref "H6") (pin "7") (pinfunction "11_7") (pintype "unspecified"))
    )
    (net (code "190") (name "dC_enable") (class "Default")
      (node (ref "DC_R1") (pin "8") (pinfunction "8_8") (pintype "unspecified"))
      (node (ref "H7") (pin "4") (pinfunction "4_4") (pintype "unspecified"))
    )
    (net (code "191") (name "dC_step") (class "Default")
      (node (ref "DC_R1") (pin "2") (pinfunction "2_2") (pintype "unspecified"))
      (node (ref "H6") (pin "9") (pinfunction "9_9") (pintype "unspecified"))
    )
    (net (code "192") (name "dG_PH_VPPH") (class "Default")
      (node (ref "DG_PH_M2") (pin "2") (pinfunction "D_2") (pintype "unspecified"))
      (node (ref "DG_PRINTHEAD1") (pin "3") (pinfunction "VPPH_3") (pintype "unspecified"))
    )
    (net (code "193") (name "dG_PH_VPPL") (class "Default")
      (node (ref "DG_PH_M1") (pin "2") (pinfunction "D_2") (pintype "unspecified"))
      (node (ref "DG_PRINTHEAD1") (pin "4") (pinfunction "VPPL_4") (pintype "unspecified"))
    )
    (net (code "194") (name "dG_PH_fault") (class "Default")
      (node (ref "DG_PRINTHEAD1") (pin "6") (pinfunction "FAULT_6") (pintype "unspecified"))
      (node (ref "U7") (pin "9") (pinfunction "39_9") (pintype "unspecified"))
    )
    (net (code "195") (name "dG_PH_fire") (class "Default")
      (node (ref "DG_PRINTHEAD1") (pin "16") (pinfunction "FIRE_16") (pintype "unspecified"))
      (node (ref "U5") (pin "11") (pinfunction "40_11") (pintype "unspecified"))
    )
    (net (code "196") (name "dG_PH_nSS1") (class "Default")
      (node (ref "DG_PRINTHEAD1") (pin "12") (pinfunction "nSS1_12") (pintype "unspecified"))
      (node (ref "U7") (pin "10") (pinfunction "37_10") (pintype "unspecified"))
    )
    (net (code "197") (name "dG_PH_nSS2") (class "Default")
      (node (ref "DG_PRINTHEAD1") (pin "1") (pinfunction "nSS2_1") (pintype "unspecified"))
      (node (ref "U5") (pin "10") (pinfunction "38_10") (pintype "unspecified"))
    )
    (net (code "198") (name "dG_PH_ready") (class "Default")
      (node (ref "DG_PRINTHEAD1") (pin "14") (pinfunction "READY_14") (pintype "unspecified"))
      (node (ref "U7") (pin "8") (pinfunction "41_8") (pintype "unspecified"))
    )
    (net (code "199") (name "dG_S") (class "Default")
      (node (ref "DG_S_R1") (pin "2") (pinfunction "2_2") (pintype "unspecified"))
      (node (ref "DG_S_R2") (pin "1") (pinfunction "1_1") (pintype "unspecified"))
      (node (ref "H9") (pin "4") (pinfunction "A3_4") (pintype "input"))
    )
    (net (code "200") (name "dG_enable") (class "Default")
      (node (ref "DG_R1") (pin "8") (pinfunction "8_8") (pintype "unspecified"))
      (node (ref "H7") (pin "5") (pinfunction "3_5") (pintype "unspecified"))
    )
    (net (code "201") (name "dG_step") (class "Default")
      (node (ref "DG_R1") (pin "2") (pinfunction "2_2") (pintype "unspecified"))
      (node (ref "H6") (pin "10") (pinfunction "8_10") (pintype "unspecified"))
    )
    (net (code "202") (name "dT_PH_VPPH") (class "Default")
      (node (ref "DT_PH_M2") (pin "2") (pinfunction "D_2") (pintype "unspecified"))
      (node (ref "DT_PRINTHEAD1") (pin "3") (pinfunction "VPPH_3") (pintype "unspecified"))
    )
    (net (code "203") (name "dT_PH_VPPL") (class "Default")
      (node (ref "DT_PH_M1") (pin "2") (pinfunction "D_2") (pintype "unspecified"))
      (node (ref "DT_PRINTHEAD1") (pin "4") (pinfunction "VPPL_4") (pintype "unspecified"))
    )
    (net (code "204") (name "dT_PH_fault") (class "Default")
      (node (ref "DT_PRINTHEAD1") (pin "6") (pinfunction "FAULT_6") (pintype "unspecified"))
      (node (ref "U5") (pin "8") (pinfunction "34_8") (pintype "unspecified"))
    )
    (net (code "205") (name "dT_PH_fire") (class "Default")
      (node (ref "DT_PRINTHEAD1") (pin "16") (pinfunction "FIRE_16") (pintype "unspecified"))
      (node (ref "U7") (pin "11") (pinfunction "35_11") (pintype "unspecified"))
    )
    (net (code "206") (name "dT_PH_nSS1") (class "Default")
      (node (ref "DT_PRINTHEAD1") (pin "12") (pinfunction "nSS1_12") (pintype "unspecified"))
      (node (ref "U5") (pin "7") (pinfunction "32_7") (pintype "unspecified"))
    )
    (net (code "207") (name "dT_PH_nSS2") (class "Default")
      (node (ref "DT_PRINTHEAD1") (pin "1") (pinfunction "nSS2_1") (pintype "unspecified"))
      (node (ref "U7") (pin "12") (pinfunction "33_12") (pintype "unspecified"))
    )
    (net (code "208") (name "dT_PH_ready") (class "Default")
      (node (ref "DT_PRINTHEAD1") (pin "14") (pinfunction "READY_14") (pintype "unspecified"))
      (node (ref "U5") (pin "9") (pinfunction "36_9") (pintype "unspecified"))
    )
    (net (code "209") (name "dT_S") (class "Default")
      (node (ref "DT_S_R1") (pin "2") (pinfunction "2_2") (pintype "unspecified"))
      (node (ref "DT_S_R2") (pin "1") (pinfunction "1_1") (pintype "unspecified"))
      (node (ref "H9") (pin "3") (pinfunction "A2_3") (pintype "input"))
    )
    (net (code "210") (name "dT_enable") (class "Default")
      (node (ref "DT_R1") (pin "8") (pinfunction "8_8") (pintype "unspecified"))
      (node (ref "H7") (pin "6") (pinfunction "2_6") (pintype "unspecified"))
    )
    (net (code "211") (name "dT_step") (class "Default")
      (node (ref "DT_R1") (pin "2") (pinfunction "2_2") (pintype "unspecified"))
      (node (ref "H7") (pin "1") (pinfunction "7_1") (pintype "unspecified"))
    )
    (net (code "212") (name "ink_direction") (class "Default")
      (node (ref "ACT_R1") (pin "1") (pinfunction "1_1") (pintype "unspecified"))
      (node (ref "DA_R1") (pin "1") (pinfunction "1_1") (pintype "unspecified"))
      (node (ref "DC_R1") (pin "1") (pinfunction "1_1") (pintype "unspecified"))
      (node (ref "DG_R1") (pin "1") (pinfunction "1_1") (pintype "unspecified"))
      (node (ref "DT_R1") (pin "1") (pinfunction "1_1") (pintype "unspecified"))
      (node (ref "H6") (pin "8") (pinfunction "10_8") (pintype "unspecified"))
    )
    (net (code "213") (name "limit_L_S") (class "Default")
      (node (ref "MEGA-A1") (pin "1") (pinfunction "A0_1") (pintype "unspecified"))
    )
    (net (code "214") (name "limit_R_S") (class "Default")
      (node (ref "MEGA-A1") (pin "2") (pinfunction "A1_2") (pintype "unspecified"))
    )
    (net (code "215") (name "linear_E") (class "Default")
      (node (ref "MEGA-SCL2") (pin "7") (pinfunction "11_7") (pintype "unspecified"))
    )
    (net (code "216") (name "linear_RX") (class "Default")
      (node (ref "MEGA-D2") (pin "4") (pinfunction "17_4") (pintype "unspecified"))
    )
    (net (code "217") (name "linear_TX") (class "Default")
      (node (ref "MEGA-D2") (pin "3") (pinfunction "16_3") (pintype "unspecified"))
    )
    (net (code "218") (name "linear_direction") (class "Default")
      (node (ref "LINEAR_R1") (pin "1") (pinfunction "1_1") (pintype "unspecified"))
    )
    (net (code "219") (name "linear_enable") (class "Default")
      (node (ref "LINEAR_R1") (pin "8") (pinfunction "8_8") (pintype "unspecified"))
    )
    (net (code "220") (name "linear_pulse") (class "Default")
      (node (ref "MEGA-D1") (pin "3") (pinfunction "5_3") (pintype "unspecified"))
    )
    (net (code "221") (name "linear_step") (class "Default")
      (node (ref "LINEAR_R1") (pin "2") (pinfunction "2_2") (pintype "unspecified"))
    )
    (net (code "222") (name "mega_D52") (class "Default")
      (node (ref "ACT_PH_T1") (pin "2") (pinfunction "B_2") (pintype "unspecified"))
      (node (ref "ACT_PH_T2") (pin "2") (pinfunction "B_2") (pintype "unspecified"))
      (node (ref "DA_PH_T1") (pin "2") (pinfunction "B_2") (pintype "unspecified"))
      (node (ref "DA_PH_T2") (pin "2") (pinfunction "B_2") (pintype "unspecified"))
      (node (ref "DC_PH_T1") (pin "2") (pinfunction "B_2") (pintype "unspecified"))
      (node (ref "DC_PH_T2") (pin "2") (pinfunction "B_2") (pintype "unspecified"))
      (node (ref "DG_PH_T1") (pin "2") (pinfunction "B_2") (pintype "unspecified"))
      (node (ref "DG_PH_T2") (pin "2") (pinfunction "B_2") (pintype "unspecified"))
      (node (ref "DT_PH_T1") (pin "2") (pinfunction "B_2") (pintype "unspecified"))
      (node (ref "DT_PH_T2") (pin "2") (pinfunction "B_2") (pintype "unspecified"))
      (node (ref "U5") (pin "17") (pinfunction "52_17") (pintype "unspecified"))
    )
    (net (code "223") (name "unconnected-(H6-12-Pad6)") (class "Default")
      (node (ref "H6") (pin "6") (pinfunction "12_6") (pintype "unspecified"))
    )
    (net (code "224") (name "unconnected-(H6-13-Pad5)") (class "Default")
      (node (ref "H6") (pin "5") (pinfunction "13_5") (pintype "unspecified"))
    )
    (net (code "225") (name "unconnected-(H6-AREF-Pad3)") (class "Default")
      (node (ref "H6") (pin "3") (pinfunction "AREF_3") (pintype "unspecified"))
    )
    (net (code "226") (name "unconnected-(H6-SCL-Pad1)") (class "Default")
      (node (ref "H6") (pin "1") (pinfunction "SCL_1") (pintype "unspecified"))
    )
    (net (code "227") (name "unconnected-(H6-SDA-Pad2)") (class "Default")
      (node (ref "H6") (pin "2") (pinfunction "SDA_2") (pintype "unspecified"))
    )
    (net (code "228") (name "unconnected-(H8-3.3V-Pad4)") (class "Default")
      (node (ref "H8") (pin "4") (pinfunction "3.3V_4") (pintype "unspecified"))
    )
    (net (code "229") (name "unconnected-(H8-IOREF-Pad2)") (class "Default")
      (node (ref "H8") (pin "2") (pinfunction "IOREF_2") (pintype "unspecified"))
    )
    (net (code "230") (name "unconnected-(H8-Pad1)") (class "Default")
      (node (ref "H8") (pin "1") (pintype "unspecified"))
    )
    (net (code "231") (name "unconnected-(MEGA-A1-A2-Pad3)") (class "Default")
      (node (ref "MEGA-A1") (pin "3") (pinfunction "A2_3") (pintype "unspecified"))
    )
    (net (code "232") (name "unconnected-(MEGA-A1-A3-Pad4)") (class "Default")
      (node (ref "MEGA-A1") (pin "4") (pinfunction "A3_4") (pintype "unspecified"))
    )
    (net (code "233") (name "unconnected-(MEGA-A1-A4-Pad5)") (class "Default")
      (node (ref "MEGA-A1") (pin "5") (pinfunction "A4_5") (pintype "unspecified"))
    )
    (net (code "234") (name "unconnected-(MEGA-A1-A5-Pad6)") (class "Default")
      (node (ref "MEGA-A1") (pin "6") (pinfunction "A5_6") (pintype "unspecified"))
    )
    (net (code "235") (name "unconnected-(MEGA-A1-A6-Pad7)") (class "Default")
      (node (ref "MEGA-A1") (pin "7") (pinfunction "A6_7") (pintype "unspecified"))
    )
    (net (code "236") (name "unconnected-(MEGA-A1-A7-Pad8)") (class "Default")
      (node (ref "MEGA-A1") (pin "8") (pinfunction "A7_8") (pintype "unspecified"))
    )
    (net (code "237") (name "unconnected-(MEGA-A2-A8-Pad1)") (class "Default")
      (node (ref "MEGA-A2") (pin "1") (pinfunction "A8_1") (pintype "unspecified"))
    )
    (net (code "238") (name "unconnected-(MEGA-A2-A9-Pad2)") (class "Default")
      (node (ref "MEGA-A2") (pin "2") (pinfunction "A9_2") (pintype "unspecified"))
    )
    (net (code "239") (name "unconnected-(MEGA-A2-A10-Pad3)") (class "Default")
      (node (ref "MEGA-A2") (pin "3") (pinfunction "A10_3") (pintype "unspecified"))
    )
    (net (code "240") (name "unconnected-(MEGA-A2-A11-Pad4)") (class "Default")
      (node (ref "MEGA-A2") (pin "4") (pinfunction "A11_4") (pintype "unspecified"))
    )
    (net (code "241") (name "unconnected-(MEGA-A2-A12-Pad5)") (class "Default")
      (node (ref "MEGA-A2") (pin "5") (pinfunction "A12_5") (pintype "unspecified"))
    )
    (net (code "242") (name "unconnected-(MEGA-A2-A13-Pad6)") (class "Default")
      (node (ref "MEGA-A2") (pin "6") (pinfunction "A13_6") (pintype "unspecified"))
    )
    (net (code "243") (name "unconnected-(MEGA-A2-A14-Pad7)") (class "Default")
      (node (ref "MEGA-A2") (pin "7") (pinfunction "A14_7") (pintype "unspecified"))
    )
    (net (code "244") (name "unconnected-(MEGA-A2-A15-Pad8)") (class "Default")
      (node (ref "MEGA-A2") (pin "8") (pinfunction "A15_8") (pintype "unspecified"))
    )
    (net (code "245") (name "unconnected-(MEGA-IOREF1-3.3V-Pad4)") (class "Default")
      (node (ref "MEGA-IOREF1") (pin "4") (pinfunction "3.3V_4") (pintype "unspecified"))
    )
    (net (code "246") (name "unconnected-(MEGA-IOREF1-IOREF-Pad2)") (class "Default")
      (node (ref "MEGA-IOREF1") (pin "2") (pinfunction "IOREF_2") (pintype "unspecified"))
    )
    (net (code "247") (name "unconnected-(MEGA-IOREF1-Pad1)") (class "Default")
      (node (ref "MEGA-IOREF1") (pin "1") (pintype "unspecified"))
    )
    (net (code "248") (name "unconnected-(MEGA-SCL2-AREF-Pad3)") (class "Default")
      (node (ref "MEGA-SCL2") (pin "3") (pinfunction "AREF_3") (pintype "unspecified"))
    )
    (net (code "249") (name "unconnected-(MEGA-SCL2-SCL-Pad1)") (class "Default")
      (node (ref "MEGA-SCL2") (pin "1") (pinfunction "SCL_1") (pintype "unspecified"))
    )
    (net (code "250") (name "unconnected-(MEGA-SCL2-SDA-Pad2)") (class "Default")
      (node (ref "MEGA-SCL2") (pin "2") (pinfunction "SDA_2") (pintype "unspecified"))
    )
    (net (code "251") (name "unconnected-(SW1-Pad2)") (class "Default")
      (node (ref "SW1") (pin "2") (pinfunction "2_2") (pintype "unspecified"))
    )
    (net (code "252") (name "unconnected-(SW1-Pad4)") (class "Default")
      (node (ref "SW1") (pin "4") (pinfunction "4_4") (pintype "unspecified"))
    )
    (net (code "253") (name "unconnected-(SW3-Pad1)") (class "Default")
      (node (ref "SW3") (pin "1") (pinfunction "1_1") (pintype "unspecified"))
    )
    (net (code "254") (name "unconnected-(SW3-Pad3)") (class "Default")
      (node (ref "SW3") (pin "3") (pinfunction "3_3") (pintype "unspecified"))
    )
    (net (code "255") (name "unconnected-(U7-53-Pad2)") (class "Default")
      (node (ref "U7") (pin "2") (pinfunction "53_2") (pintype "unspecified"))
    )
    (net (code "256") (name "unconnected-(U7-none-Pad18)") (class "Default")
      (node (ref "U7") (pin "18") (pinfunction "none_18") (pintype "unspecified"))
    )
    (net (code "257") (name "valve") (class "Default")
      (node (ref "MEGA-SCL2") (pin "5") (pinfunction "13_5") (pintype "unspecified"))
      (node (ref "R6") (pin "2") (pinfunction "2_2") (pintype "unspecified"))
    )
    (net (code "258") (name "wash_E") (class "Default")
      (node (ref "MEGA-SCL2") (pin "9") (pinfunction "9_9") (pintype "unspecified"))
    )
    (net (code "259") (name "wash_enable") (class "Default")
      (node (ref "WASH_R1") (pin "8") (pinfunction "8_8") (pintype "unspecified"))
    )
    (net (code "260") (name "wash_pulse") (class "Default")
      (node (ref "MEGA-D1") (pin "5") (pinfunction "3_5") (pintype "unspecified"))
    )
    (net (code "261") (name "wash_step") (class "Default")
      (node (ref "WASH_R1") (pin "2") (pinfunction "2_2") (pintype "unspecified"))
    )
    (net (code "262") (name "waste_E") (class "Default")
      (node (ref "MEGA-SCL2") (pin "6") (pinfunction "12_6") (pintype "unspecified"))
    )
    (net (code "263") (name "waste_RX") (class "Default")
      (node (ref "MEGA-D2") (pin "2") (pinfunction "15_2") (pintype "unspecified"))
    )
    (net (code "264") (name "waste_TX") (class "Default")
      (node (ref "MEGA-D2") (pin "1") (pinfunction "14_1") (pintype "unspecified"))
    )
    (net (code "265") (name "waste_enable") (class "Default")
      (node (ref "WASTE1_R") (pin "8") (pinfunction "8_8") (pintype "unspecified"))
      (node (ref "WASTE2_R") (pin "8") (pinfunction "8_8") (pintype "unspecified"))
    )
    (net (code "266") (name "waste_pulse") (class "Default")
      (node (ref "MEGA-D1") (pin "2") (pinfunction "6_2") (pintype "unspecified"))
    )
    (net (code "267") (name "waste_step") (class "Default")
      (node (ref "WASTE1_R") (pin "2") (pinfunction "2_2") (pintype "unspecified"))
      (node (ref "WASTE2_R") (pin "2") (pinfunction "2_2") (pintype "unspecified"))
    )
  )
)
